# Schematic.net
KiCad netlist of a schematic drawn in Altium Designer
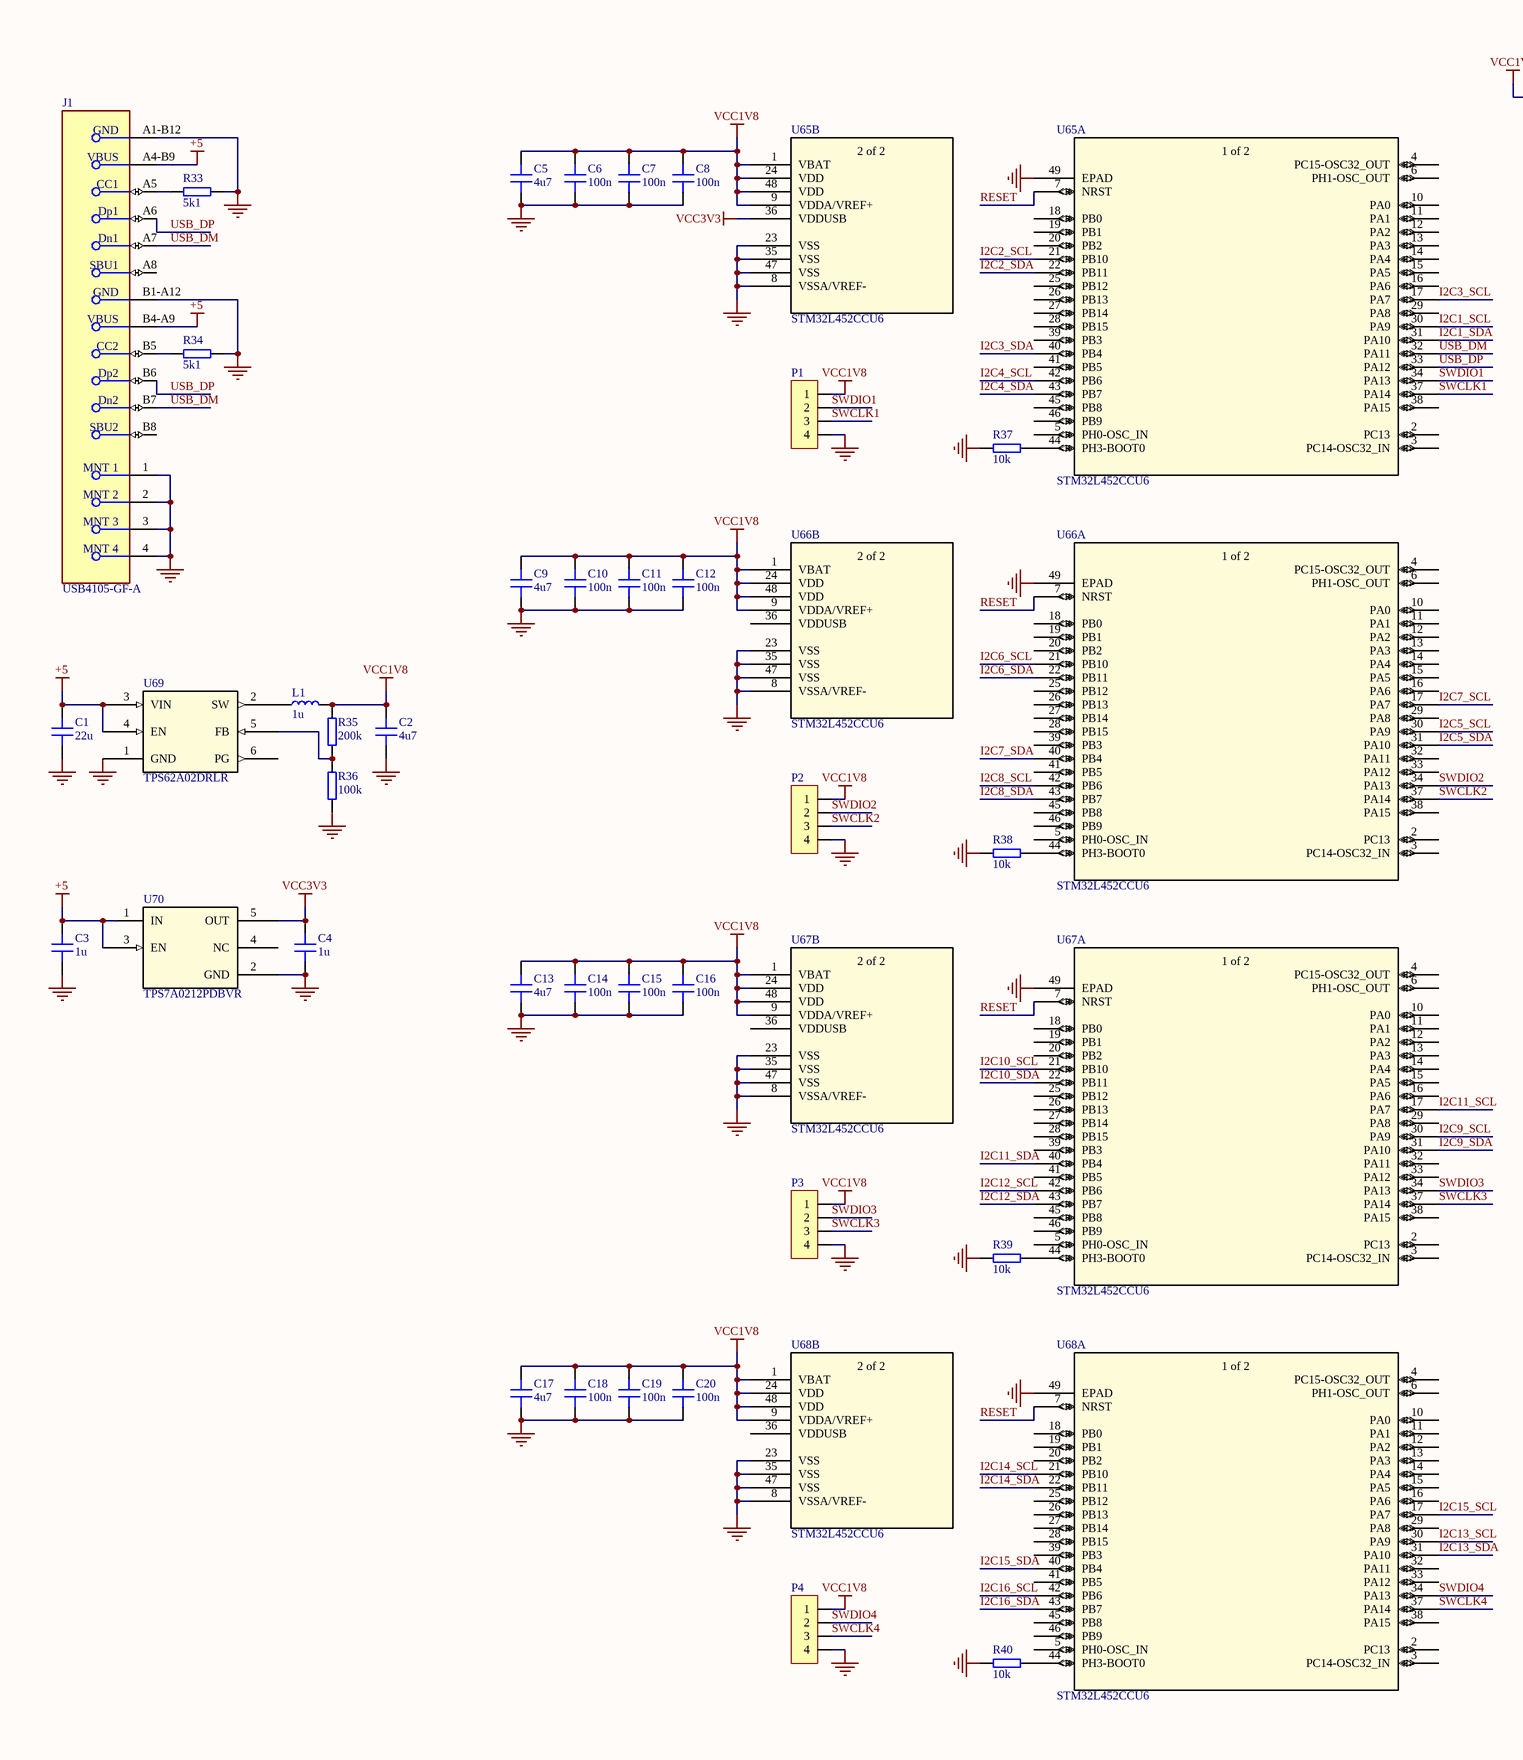
[diagram p0: Schematic.SchDoc, left]
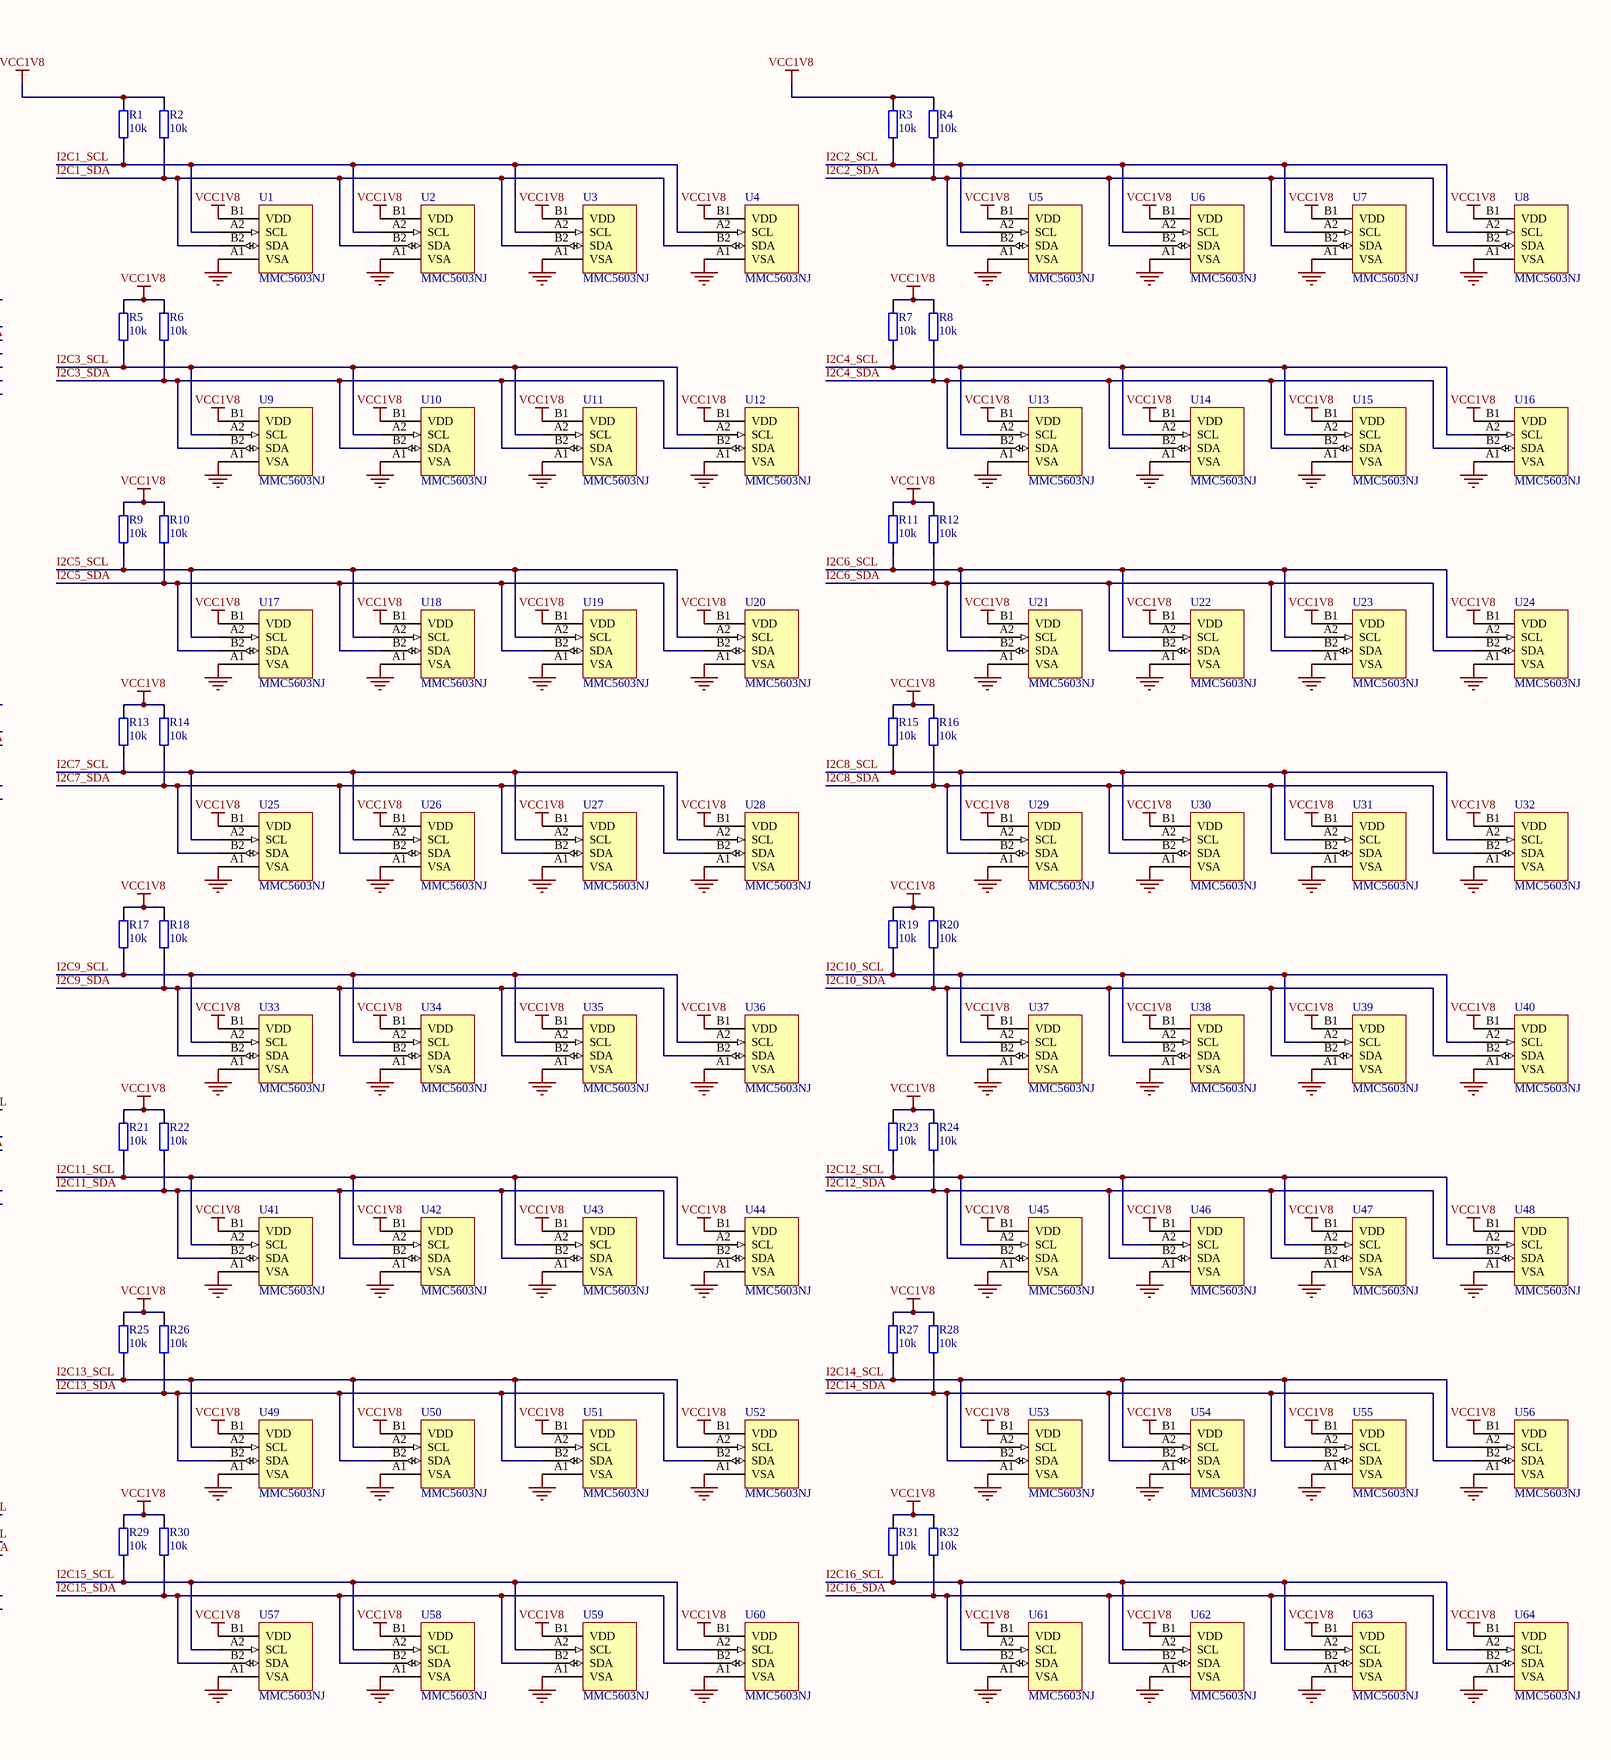
[diagram p1: Schematic.SchDoc, right]

(export (version "E")
  (design (tool "Eeschema 10.0.6"))
  (components
    (comp (ref "C1")
      (value "22u")
      (footprint "CAP_0603")
      (description "Capacitor SMD 0603")
      (fields (field (name "VOLTAGE") "50V"))
      (libsource (lib "symbols") (part "CAP_0603"))
    )
    (comp (ref "C2")
      (value "4u7")
      (footprint "CAP_0603")
      (description "Capacitor SMD 0603")
      (fields (field (name "VOLTAGE") "50V"))
      (libsource (lib "symbols") (part "CAP_0603"))
    )
    (comp (ref "C3")
      (value "1u")
      (footprint "CAP_0603")
      (description "Capacitor SMD 0603")
      (fields (field (name "VOLTAGE") "50V"))
      (libsource (lib "symbols") (part "CAP_0603"))
    )
    (comp (ref "C4")
      (value "1u")
      (footprint "CAP_0603")
      (description "Capacitor SMD 0603")
      (fields (field (name "VOLTAGE") "50V"))
      (libsource (lib "symbols") (part "CAP_0603"))
    )
    (comp (ref "C5")
      (value "4u7")
      (footprint "CAP_0603")
      (description "Capacitor SMD 0603")
      (fields (field (name "VOLTAGE") "50V"))
      (libsource (lib "symbols") (part "CAP_0603"))
    )
    (comp (ref "C6")
      (value "100n")
      (footprint "CAP_0402")
      (description "Capacitor SMD 0402")
      (fields (field (name "VOLTAGE") "50V"))
      (libsource (lib "symbols") (part "CAP_0402"))
    )
    (comp (ref "C7")
      (value "100n")
      (footprint "CAP_0402")
      (description "Capacitor SMD 0402")
      (fields (field (name "VOLTAGE") "50V"))
      (libsource (lib "symbols") (part "CAP_0402"))
    )
    (comp (ref "C8")
      (value "100n")
      (footprint "CAP_0402")
      (description "Capacitor SMD 0402")
      (fields (field (name "VOLTAGE") "50V"))
      (libsource (lib "symbols") (part "CAP_0402"))
    )
    (comp (ref "C9")
      (value "4u7")
      (footprint "CAP_0603")
      (description "Capacitor SMD 0603")
      (fields (field (name "VOLTAGE") "50V"))
      (libsource (lib "symbols") (part "CAP_0603"))
    )
    (comp (ref "C10")
      (value "100n")
      (footprint "CAP_0402")
      (description "Capacitor SMD 0402")
      (fields (field (name "VOLTAGE") "50V"))
      (libsource (lib "symbols") (part "CAP_0402"))
    )
    (comp (ref "C11")
      (value "100n")
      (footprint "CAP_0402")
      (description "Capacitor SMD 0402")
      (fields (field (name "VOLTAGE") "50V"))
      (libsource (lib "symbols") (part "CAP_0402"))
    )
    (comp (ref "C12")
      (value "100n")
      (footprint "CAP_0402")
      (description "Capacitor SMD 0402")
      (fields (field (name "VOLTAGE") "50V"))
      (libsource (lib "symbols") (part "CAP_0402"))
    )
    (comp (ref "C13")
      (value "4u7")
      (footprint "CAP_0603")
      (description "Capacitor SMD 0603")
      (fields (field (name "VOLTAGE") "50V"))
      (libsource (lib "symbols") (part "CAP_0603"))
    )
    (comp (ref "C14")
      (value "100n")
      (footprint "CAP_0402")
      (description "Capacitor SMD 0402")
      (fields (field (name "VOLTAGE") "50V"))
      (libsource (lib "symbols") (part "CAP_0402"))
    )
    (comp (ref "C15")
      (value "100n")
      (footprint "CAP_0402")
      (description "Capacitor SMD 0402")
      (fields (field (name "VOLTAGE") "50V"))
      (libsource (lib "symbols") (part "CAP_0402"))
    )
    (comp (ref "C16")
      (value "100n")
      (footprint "CAP_0402")
      (description "Capacitor SMD 0402")
      (fields (field (name "VOLTAGE") "50V"))
      (libsource (lib "symbols") (part "CAP_0402"))
    )
    (comp (ref "C17")
      (value "4u7")
      (footprint "CAP_0603")
      (description "Capacitor SMD 0603")
      (fields (field (name "VOLTAGE") "50V"))
      (libsource (lib "symbols") (part "CAP_0603"))
    )
    (comp (ref "C18")
      (value "100n")
      (footprint "CAP_0402")
      (description "Capacitor SMD 0402")
      (fields (field (name "VOLTAGE") "50V"))
      (libsource (lib "symbols") (part "CAP_0402"))
    )
    (comp (ref "C19")
      (value "100n")
      (footprint "CAP_0402")
      (description "Capacitor SMD 0402")
      (fields (field (name "VOLTAGE") "50V"))
      (libsource (lib "symbols") (part "CAP_0402"))
    )
    (comp (ref "C20")
      (value "100n")
      (footprint "CAP_0402")
      (description "Capacitor SMD 0402")
      (fields (field (name "VOLTAGE") "50V"))
      (libsource (lib "symbols") (part "CAP_0402"))
    )
    (comp (ref "J1")
      (value "USB4105-GF-A")
      (footprint "FP-USB4105-GF-A-MFG")
      (description "CONN RCPT USB2.0 TYPEC 5A")
      (fields
        (field (name "MANUFACTURER") "GCT")
        (field (name "OCTOPART") "https://octopart.com/usb4105-gf-a-gct-106627878")
      )
      (libsource (lib "symbols") (part "CMP-245163-000001-1"))
    )
    (comp (ref "L1")
      (value "1u")
      (footprint "IND_0603")
      (description "Inductor SMD 0603")
      (libsource (lib "symbols") (part "IND_0603"))
    )
    (comp (ref "P1")
      (value "PIN_1.27x4")
      (footprint "PIN_1.27x4")
      (libsource (lib "symbols") (part "PIN_1.27x4"))
    )
    (comp (ref "P2")
      (value "PIN_1.27x4")
      (footprint "PIN_1.27x4")
      (libsource (lib "symbols") (part "PIN_1.27x4"))
    )
    (comp (ref "P3")
      (value "PIN_1.27x4")
      (footprint "PIN_1.27x4")
      (libsource (lib "symbols") (part "PIN_1.27x4"))
    )
    (comp (ref "P4")
      (value "PIN_1.27x4")
      (footprint "PIN_1.27x4")
      (libsource (lib "symbols") (part "PIN_1.27x4"))
    )
    (comp (ref "R1")
      (value "10k")
      (footprint "RES_0402_RF")
      (description "Resistor SMD 0402")
      (libsource (lib "symbols") (part "RES_0402"))
    )
    (comp (ref "R2")
      (value "10k")
      (footprint "RES_0402_RF")
      (description "Resistor SMD 0402")
      (libsource (lib "symbols") (part "RES_0402"))
    )
    (comp (ref "R3")
      (value "10k")
      (footprint "RES_0402_RF")
      (description "Resistor SMD 0402")
      (libsource (lib "symbols") (part "RES_0402"))
    )
    (comp (ref "R4")
      (value "10k")
      (footprint "RES_0402_RF")
      (description "Resistor SMD 0402")
      (libsource (lib "symbols") (part "RES_0402"))
    )
    (comp (ref "R5")
      (value "10k")
      (footprint "RES_0402_RF")
      (description "Resistor SMD 0402")
      (libsource (lib "symbols") (part "RES_0402"))
    )
    (comp (ref "R6")
      (value "10k")
      (footprint "RES_0402_RF")
      (description "Resistor SMD 0402")
      (libsource (lib "symbols") (part "RES_0402"))
    )
    (comp (ref "R7")
      (value "10k")
      (footprint "RES_0402_RF")
      (description "Resistor SMD 0402")
      (libsource (lib "symbols") (part "RES_0402"))
    )
    (comp (ref "R8")
      (value "10k")
      (footprint "RES_0402_RF")
      (description "Resistor SMD 0402")
      (libsource (lib "symbols") (part "RES_0402"))
    )
    (comp (ref "R9")
      (value "10k")
      (footprint "RES_0402_RF")
      (description "Resistor SMD 0402")
      (libsource (lib "symbols") (part "RES_0402"))
    )
    (comp (ref "R10")
      (value "10k")
      (footprint "RES_0402_RF")
      (description "Resistor SMD 0402")
      (libsource (lib "symbols") (part "RES_0402"))
    )
    (comp (ref "R11")
      (value "10k")
      (footprint "RES_0402_RF")
      (description "Resistor SMD 0402")
      (libsource (lib "symbols") (part "RES_0402"))
    )
    (comp (ref "R12")
      (value "10k")
      (footprint "RES_0402_RF")
      (description "Resistor SMD 0402")
      (libsource (lib "symbols") (part "RES_0402"))
    )
    (comp (ref "R13")
      (value "10k")
      (footprint "RES_0402_RF")
      (description "Resistor SMD 0402")
      (libsource (lib "symbols") (part "RES_0402"))
    )
    (comp (ref "R14")
      (value "10k")
      (footprint "RES_0402_RF")
      (description "Resistor SMD 0402")
      (libsource (lib "symbols") (part "RES_0402"))
    )
    (comp (ref "R15")
      (value "10k")
      (footprint "RES_0402_RF")
      (description "Resistor SMD 0402")
      (libsource (lib "symbols") (part "RES_0402"))
    )
    (comp (ref "R16")
      (value "10k")
      (footprint "RES_0402_RF")
      (description "Resistor SMD 0402")
      (libsource (lib "symbols") (part "RES_0402"))
    )
    (comp (ref "R17")
      (value "10k")
      (footprint "RES_0402_RF")
      (description "Resistor SMD 0402")
      (libsource (lib "symbols") (part "RES_0402"))
    )
    (comp (ref "R18")
      (value "10k")
      (footprint "RES_0402_RF")
      (description "Resistor SMD 0402")
      (libsource (lib "symbols") (part "RES_0402"))
    )
    (comp (ref "R19")
      (value "10k")
      (footprint "RES_0402_RF")
      (description "Resistor SMD 0402")
      (libsource (lib "symbols") (part "RES_0402"))
    )
    (comp (ref "R20")
      (value "10k")
      (footprint "RES_0402_RF")
      (description "Resistor SMD 0402")
      (libsource (lib "symbols") (part "RES_0402"))
    )
    (comp (ref "R21")
      (value "10k")
      (footprint "RES_0402_RF")
      (description "Resistor SMD 0402")
      (libsource (lib "symbols") (part "RES_0402"))
    )
    (comp (ref "R22")
      (value "10k")
      (footprint "RES_0402_RF")
      (description "Resistor SMD 0402")
      (libsource (lib "symbols") (part "RES_0402"))
    )
    (comp (ref "R23")
      (value "10k")
      (footprint "RES_0402_RF")
      (description "Resistor SMD 0402")
      (libsource (lib "symbols") (part "RES_0402"))
    )
    (comp (ref "R24")
      (value "10k")
      (footprint "RES_0402_RF")
      (description "Resistor SMD 0402")
      (libsource (lib "symbols") (part "RES_0402"))
    )
    (comp (ref "R25")
      (value "10k")
      (footprint "RES_0402_RF")
      (description "Resistor SMD 0402")
      (libsource (lib "symbols") (part "RES_0402"))
    )
    (comp (ref "R26")
      (value "10k")
      (footprint "RES_0402_RF")
      (description "Resistor SMD 0402")
      (libsource (lib "symbols") (part "RES_0402"))
    )
    (comp (ref "R27")
      (value "10k")
      (footprint "RES_0402_RF")
      (description "Resistor SMD 0402")
      (libsource (lib "symbols") (part "RES_0402"))
    )
    (comp (ref "R28")
      (value "10k")
      (footprint "RES_0402_RF")
      (description "Resistor SMD 0402")
      (libsource (lib "symbols") (part "RES_0402"))
    )
    (comp (ref "R29")
      (value "10k")
      (footprint "RES_0402_RF")
      (description "Resistor SMD 0402")
      (libsource (lib "symbols") (part "RES_0402"))
    )
    (comp (ref "R30")
      (value "10k")
      (footprint "RES_0402_RF")
      (description "Resistor SMD 0402")
      (libsource (lib "symbols") (part "RES_0402"))
    )
    (comp (ref "R31")
      (value "10k")
      (footprint "RES_0402_RF")
      (description "Resistor SMD 0402")
      (libsource (lib "symbols") (part "RES_0402"))
    )
    (comp (ref "R32")
      (value "10k")
      (footprint "RES_0402_RF")
      (description "Resistor SMD 0402")
      (libsource (lib "symbols") (part "RES_0402"))
    )
    (comp (ref "R33")
      (value "5k1")
      (footprint "RES_0402_RF")
      (description "Resistor SMD 0402")
      (libsource (lib "symbols") (part "RES_0402"))
    )
    (comp (ref "R34")
      (value "5k1")
      (footprint "RES_0402_RF")
      (description "Resistor SMD 0402")
      (libsource (lib "symbols") (part "RES_0402"))
    )
    (comp (ref "R35")
      (value "200k")
      (footprint "RES_0402_RF")
      (description "Resistor SMD 0402")
      (libsource (lib "symbols") (part "RES_0402"))
    )
    (comp (ref "R36")
      (value "100k")
      (footprint "RES_0402_RF")
      (description "Resistor SMD 0402")
      (libsource (lib "symbols") (part "RES_0402"))
    )
    (comp (ref "R37")
      (value "10k")
      (footprint "RES_0402_RF")
      (description "Resistor SMD 0402")
      (libsource (lib "symbols") (part "RES_0402"))
    )
    (comp (ref "R38")
      (value "10k")
      (footprint "RES_0402_RF")
      (description "Resistor SMD 0402")
      (libsource (lib "symbols") (part "RES_0402"))
    )
    (comp (ref "R39")
      (value "10k")
      (footprint "RES_0402_RF")
      (description "Resistor SMD 0402")
      (libsource (lib "symbols") (part "RES_0402"))
    )
    (comp (ref "R40")
      (value "10k")
      (footprint "RES_0402_RF")
      (description "Resistor SMD 0402")
      (libsource (lib "symbols") (part "RES_0402"))
    )
    (comp (ref "U1")
      (value "MMC5603NJ")
      (footprint "WLP4x2")
      (description "3-AXIS Amr Magnetic Sensor")
      (fields (field (name "MANUFACTURER") "Memsic"))
      (libsource (lib "symbols") (part "MMC5603NJ"))
    )
    (comp (ref "U2")
      (value "MMC5603NJ")
      (footprint "WLP4x2")
      (description "3-AXIS Amr Magnetic Sensor")
      (fields (field (name "MANUFACTURER") "Memsic"))
      (libsource (lib "symbols") (part "MMC5603NJ"))
    )
    (comp (ref "U3")
      (value "MMC5603NJ")
      (footprint "WLP4x2")
      (description "3-AXIS Amr Magnetic Sensor")
      (fields (field (name "MANUFACTURER") "Memsic"))
      (libsource (lib "symbols") (part "MMC5603NJ"))
    )
    (comp (ref "U4")
      (value "MMC5603NJ")
      (footprint "WLP4x2")
      (description "3-AXIS Amr Magnetic Sensor")
      (fields (field (name "MANUFACTURER") "Memsic"))
      (libsource (lib "symbols") (part "MMC5603NJ"))
    )
    (comp (ref "U5")
      (value "MMC5603NJ")
      (footprint "WLP4x2")
      (description "3-AXIS Amr Magnetic Sensor")
      (fields (field (name "MANUFACTURER") "Memsic"))
      (libsource (lib "symbols") (part "MMC5603NJ"))
    )
    (comp (ref "U6")
      (value "MMC5603NJ")
      (footprint "WLP4x2")
      (description "3-AXIS Amr Magnetic Sensor")
      (fields (field (name "MANUFACTURER") "Memsic"))
      (libsource (lib "symbols") (part "MMC5603NJ"))
    )
    (comp (ref "U7")
      (value "MMC5603NJ")
      (footprint "WLP4x2")
      (description "3-AXIS Amr Magnetic Sensor")
      (fields (field (name "MANUFACTURER") "Memsic"))
      (libsource (lib "symbols") (part "MMC5603NJ"))
    )
    (comp (ref "U8")
      (value "MMC5603NJ")
      (footprint "WLP4x2")
      (description "3-AXIS Amr Magnetic Sensor")
      (fields (field (name "MANUFACTURER") "Memsic"))
      (libsource (lib "symbols") (part "MMC5603NJ"))
    )
    (comp (ref "U9")
      (value "MMC5603NJ")
      (footprint "WLP4x2")
      (description "3-AXIS Amr Magnetic Sensor")
      (fields (field (name "MANUFACTURER") "Memsic"))
      (libsource (lib "symbols") (part "MMC5603NJ"))
    )
    (comp (ref "U10")
      (value "MMC5603NJ")
      (footprint "WLP4x2")
      (description "3-AXIS Amr Magnetic Sensor")
      (fields (field (name "MANUFACTURER") "Memsic"))
      (libsource (lib "symbols") (part "MMC5603NJ"))
    )
    (comp (ref "U11")
      (value "MMC5603NJ")
      (footprint "WLP4x2")
      (description "3-AXIS Amr Magnetic Sensor")
      (fields (field (name "MANUFACTURER") "Memsic"))
      (libsource (lib "symbols") (part "MMC5603NJ"))
    )
    (comp (ref "U12")
      (value "MMC5603NJ")
      (footprint "WLP4x2")
      (description "3-AXIS Amr Magnetic Sensor")
      (fields (field (name "MANUFACTURER") "Memsic"))
      (libsource (lib "symbols") (part "MMC5603NJ"))
    )
    (comp (ref "U13")
      (value "MMC5603NJ")
      (footprint "WLP4x2")
      (description "3-AXIS Amr Magnetic Sensor")
      (fields (field (name "MANUFACTURER") "Memsic"))
      (libsource (lib "symbols") (part "MMC5603NJ"))
    )
    (comp (ref "U14")
      (value "MMC5603NJ")
      (footprint "WLP4x2")
      (description "3-AXIS Amr Magnetic Sensor")
      (fields (field (name "MANUFACTURER") "Memsic"))
      (libsource (lib "symbols") (part "MMC5603NJ"))
    )
    (comp (ref "U15")
      (value "MMC5603NJ")
      (footprint "WLP4x2")
      (description "3-AXIS Amr Magnetic Sensor")
      (fields (field (name "MANUFACTURER") "Memsic"))
      (libsource (lib "symbols") (part "MMC5603NJ"))
    )
    (comp (ref "U16")
      (value "MMC5603NJ")
      (footprint "WLP4x2")
      (description "3-AXIS Amr Magnetic Sensor")
      (fields (field (name "MANUFACTURER") "Memsic"))
      (libsource (lib "symbols") (part "MMC5603NJ"))
    )
    (comp (ref "U17")
      (value "MMC5603NJ")
      (footprint "WLP4x2")
      (description "3-AXIS Amr Magnetic Sensor")
      (fields (field (name "MANUFACTURER") "Memsic"))
      (libsource (lib "symbols") (part "MMC5603NJ"))
    )
    (comp (ref "U18")
      (value "MMC5603NJ")
      (footprint "WLP4x2")
      (description "3-AXIS Amr Magnetic Sensor")
      (fields (field (name "MANUFACTURER") "Memsic"))
      (libsource (lib "symbols") (part "MMC5603NJ"))
    )
    (comp (ref "U19")
      (value "MMC5603NJ")
      (footprint "WLP4x2")
      (description "3-AXIS Amr Magnetic Sensor")
      (fields (field (name "MANUFACTURER") "Memsic"))
      (libsource (lib "symbols") (part "MMC5603NJ"))
    )
    (comp (ref "U20")
      (value "MMC5603NJ")
      (footprint "WLP4x2")
      (description "3-AXIS Amr Magnetic Sensor")
      (fields (field (name "MANUFACTURER") "Memsic"))
      (libsource (lib "symbols") (part "MMC5603NJ"))
    )
    (comp (ref "U21")
      (value "MMC5603NJ")
      (footprint "WLP4x2")
      (description "3-AXIS Amr Magnetic Sensor")
      (fields (field (name "MANUFACTURER") "Memsic"))
      (libsource (lib "symbols") (part "MMC5603NJ"))
    )
    (comp (ref "U22")
      (value "MMC5603NJ")
      (footprint "WLP4x2")
      (description "3-AXIS Amr Magnetic Sensor")
      (fields (field (name "MANUFACTURER") "Memsic"))
      (libsource (lib "symbols") (part "MMC5603NJ"))
    )
    (comp (ref "U23")
      (value "MMC5603NJ")
      (footprint "WLP4x2")
      (description "3-AXIS Amr Magnetic Sensor")
      (fields (field (name "MANUFACTURER") "Memsic"))
      (libsource (lib "symbols") (part "MMC5603NJ"))
    )
    (comp (ref "U24")
      (value "MMC5603NJ")
      (footprint "WLP4x2")
      (description "3-AXIS Amr Magnetic Sensor")
      (fields (field (name "MANUFACTURER") "Memsic"))
      (libsource (lib "symbols") (part "MMC5603NJ"))
    )
    (comp (ref "U25")
      (value "MMC5603NJ")
      (footprint "WLP4x2")
      (description "3-AXIS Amr Magnetic Sensor")
      (fields (field (name "MANUFACTURER") "Memsic"))
      (libsource (lib "symbols") (part "MMC5603NJ"))
    )
    (comp (ref "U26")
      (value "MMC5603NJ")
      (footprint "WLP4x2")
      (description "3-AXIS Amr Magnetic Sensor")
      (fields (field (name "MANUFACTURER") "Memsic"))
      (libsource (lib "symbols") (part "MMC5603NJ"))
    )
    (comp (ref "U27")
      (value "MMC5603NJ")
      (footprint "WLP4x2")
      (description "3-AXIS Amr Magnetic Sensor")
      (fields (field (name "MANUFACTURER") "Memsic"))
      (libsource (lib "symbols") (part "MMC5603NJ"))
    )
    (comp (ref "U28")
      (value "MMC5603NJ")
      (footprint "WLP4x2")
      (description "3-AXIS Amr Magnetic Sensor")
      (fields (field (name "MANUFACTURER") "Memsic"))
      (libsource (lib "symbols") (part "MMC5603NJ"))
    )
    (comp (ref "U29")
      (value "MMC5603NJ")
      (footprint "WLP4x2")
      (description "3-AXIS Amr Magnetic Sensor")
      (fields (field (name "MANUFACTURER") "Memsic"))
      (libsource (lib "symbols") (part "MMC5603NJ"))
    )
    (comp (ref "U30")
      (value "MMC5603NJ")
      (footprint "WLP4x2")
      (description "3-AXIS Amr Magnetic Sensor")
      (fields (field (name "MANUFACTURER") "Memsic"))
      (libsource (lib "symbols") (part "MMC5603NJ"))
    )
    (comp (ref "U31")
      (value "MMC5603NJ")
      (footprint "WLP4x2")
      (description "3-AXIS Amr Magnetic Sensor")
      (fields (field (name "MANUFACTURER") "Memsic"))
      (libsource (lib "symbols") (part "MMC5603NJ"))
    )
    (comp (ref "U32")
      (value "MMC5603NJ")
      (footprint "WLP4x2")
      (description "3-AXIS Amr Magnetic Sensor")
      (fields (field (name "MANUFACTURER") "Memsic"))
      (libsource (lib "symbols") (part "MMC5603NJ"))
    )
    (comp (ref "U33")
      (value "MMC5603NJ")
      (footprint "WLP4x2")
      (description "3-AXIS Amr Magnetic Sensor")
      (fields (field (name "MANUFACTURER") "Memsic"))
      (libsource (lib "symbols") (part "MMC5603NJ"))
    )
    (comp (ref "U34")
      (value "MMC5603NJ")
      (footprint "WLP4x2")
      (description "3-AXIS Amr Magnetic Sensor")
      (fields (field (name "MANUFACTURER") "Memsic"))
      (libsource (lib "symbols") (part "MMC5603NJ"))
    )
    (comp (ref "U35")
      (value "MMC5603NJ")
      (footprint "WLP4x2")
      (description "3-AXIS Amr Magnetic Sensor")
      (fields (field (name "MANUFACTURER") "Memsic"))
      (libsource (lib "symbols") (part "MMC5603NJ"))
    )
    (comp (ref "U36")
      (value "MMC5603NJ")
      (footprint "WLP4x2")
      (description "3-AXIS Amr Magnetic Sensor")
      (fields (field (name "MANUFACTURER") "Memsic"))
      (libsource (lib "symbols") (part "MMC5603NJ"))
    )
    (comp (ref "U37")
      (value "MMC5603NJ")
      (footprint "WLP4x2")
      (description "3-AXIS Amr Magnetic Sensor")
      (fields (field (name "MANUFACTURER") "Memsic"))
      (libsource (lib "symbols") (part "MMC5603NJ"))
    )
    (comp (ref "U38")
      (value "MMC5603NJ")
      (footprint "WLP4x2")
      (description "3-AXIS Amr Magnetic Sensor")
      (fields (field (name "MANUFACTURER") "Memsic"))
      (libsource (lib "symbols") (part "MMC5603NJ"))
    )
    (comp (ref "U39")
      (value "MMC5603NJ")
      (footprint "WLP4x2")
      (description "3-AXIS Amr Magnetic Sensor")
      (fields (field (name "MANUFACTURER") "Memsic"))
      (libsource (lib "symbols") (part "MMC5603NJ"))
    )
    (comp (ref "U40")
      (value "MMC5603NJ")
      (footprint "WLP4x2")
      (description "3-AXIS Amr Magnetic Sensor")
      (fields (field (name "MANUFACTURER") "Memsic"))
      (libsource (lib "symbols") (part "MMC5603NJ"))
    )
    (comp (ref "U41")
      (value "MMC5603NJ")
      (footprint "WLP4x2")
      (description "3-AXIS Amr Magnetic Sensor")
      (fields (field (name "MANUFACTURER") "Memsic"))
      (libsource (lib "symbols") (part "MMC5603NJ"))
    )
    (comp (ref "U42")
      (value "MMC5603NJ")
      (footprint "WLP4x2")
      (description "3-AXIS Amr Magnetic Sensor")
      (fields (field (name "MANUFACTURER") "Memsic"))
      (libsource (lib "symbols") (part "MMC5603NJ"))
    )
    (comp (ref "U43")
      (value "MMC5603NJ")
      (footprint "WLP4x2")
      (description "3-AXIS Amr Magnetic Sensor")
      (fields (field (name "MANUFACTURER") "Memsic"))
      (libsource (lib "symbols") (part "MMC5603NJ"))
    )
    (comp (ref "U44")
      (value "MMC5603NJ")
      (footprint "WLP4x2")
      (description "3-AXIS Amr Magnetic Sensor")
      (fields (field (name "MANUFACTURER") "Memsic"))
      (libsource (lib "symbols") (part "MMC5603NJ"))
    )
    (comp (ref "U45")
      (value "MMC5603NJ")
      (footprint "WLP4x2")
      (description "3-AXIS Amr Magnetic Sensor")
      (fields (field (name "MANUFACTURER") "Memsic"))
      (libsource (lib "symbols") (part "MMC5603NJ"))
    )
    (comp (ref "U46")
      (value "MMC5603NJ")
      (footprint "WLP4x2")
      (description "3-AXIS Amr Magnetic Sensor")
      (fields (field (name "MANUFACTURER") "Memsic"))
      (libsource (lib "symbols") (part "MMC5603NJ"))
    )
    (comp (ref "U47")
      (value "MMC5603NJ")
      (footprint "WLP4x2")
      (description "3-AXIS Amr Magnetic Sensor")
      (fields (field (name "MANUFACTURER") "Memsic"))
      (libsource (lib "symbols") (part "MMC5603NJ"))
    )
    (comp (ref "U48")
      (value "MMC5603NJ")
      (footprint "WLP4x2")
      (description "3-AXIS Amr Magnetic Sensor")
      (fields (field (name "MANUFACTURER") "Memsic"))
      (libsource (lib "symbols") (part "MMC5603NJ"))
    )
    (comp (ref "U49")
      (value "MMC5603NJ")
      (footprint "WLP4x2")
      (description "3-AXIS Amr Magnetic Sensor")
      (fields (field (name "MANUFACTURER") "Memsic"))
      (libsource (lib "symbols") (part "MMC5603NJ"))
    )
    (comp (ref "U50")
      (value "MMC5603NJ")
      (footprint "WLP4x2")
      (description "3-AXIS Amr Magnetic Sensor")
      (fields (field (name "MANUFACTURER") "Memsic"))
      (libsource (lib "symbols") (part "MMC5603NJ"))
    )
    (comp (ref "U51")
      (value "MMC5603NJ")
      (footprint "WLP4x2")
      (description "3-AXIS Amr Magnetic Sensor")
      (fields (field (name "MANUFACTURER") "Memsic"))
      (libsource (lib "symbols") (part "MMC5603NJ"))
    )
    (comp (ref "U52")
      (value "MMC5603NJ")
      (footprint "WLP4x2")
      (description "3-AXIS Amr Magnetic Sensor")
      (fields (field (name "MANUFACTURER") "Memsic"))
      (libsource (lib "symbols") (part "MMC5603NJ"))
    )
    (comp (ref "U53")
      (value "MMC5603NJ")
      (footprint "WLP4x2")
      (description "3-AXIS Amr Magnetic Sensor")
      (fields (field (name "MANUFACTURER") "Memsic"))
      (libsource (lib "symbols") (part "MMC5603NJ"))
    )
    (comp (ref "U54")
      (value "MMC5603NJ")
      (footprint "WLP4x2")
      (description "3-AXIS Amr Magnetic Sensor")
      (fields (field (name "MANUFACTURER") "Memsic"))
      (libsource (lib "symbols") (part "MMC5603NJ"))
    )
    (comp (ref "U55")
      (value "MMC5603NJ")
      (footprint "WLP4x2")
      (description "3-AXIS Amr Magnetic Sensor")
      (fields (field (name "MANUFACTURER") "Memsic"))
      (libsource (lib "symbols") (part "MMC5603NJ"))
    )
    (comp (ref "U56")
      (value "MMC5603NJ")
      (footprint "WLP4x2")
      (description "3-AXIS Amr Magnetic Sensor")
      (fields (field (name "MANUFACTURER") "Memsic"))
      (libsource (lib "symbols") (part "MMC5603NJ"))
    )
    (comp (ref "U57")
      (value "MMC5603NJ")
      (footprint "WLP4x2")
      (description "3-AXIS Amr Magnetic Sensor")
      (fields (field (name "MANUFACTURER") "Memsic"))
      (libsource (lib "symbols") (part "MMC5603NJ"))
    )
    (comp (ref "U58")
      (value "MMC5603NJ")
      (footprint "WLP4x2")
      (description "3-AXIS Amr Magnetic Sensor")
      (fields (field (name "MANUFACTURER") "Memsic"))
      (libsource (lib "symbols") (part "MMC5603NJ"))
    )
    (comp (ref "U59")
      (value "MMC5603NJ")
      (footprint "WLP4x2")
      (description "3-AXIS Amr Magnetic Sensor")
      (fields (field (name "MANUFACTURER") "Memsic"))
      (libsource (lib "symbols") (part "MMC5603NJ"))
    )
    (comp (ref "U60")
      (value "MMC5603NJ")
      (footprint "WLP4x2")
      (description "3-AXIS Amr Magnetic Sensor")
      (fields (field (name "MANUFACTURER") "Memsic"))
      (libsource (lib "symbols") (part "MMC5603NJ"))
    )
    (comp (ref "U61")
      (value "MMC5603NJ")
      (footprint "WLP4x2")
      (description "3-AXIS Amr Magnetic Sensor")
      (fields (field (name "MANUFACTURER") "Memsic"))
      (libsource (lib "symbols") (part "MMC5603NJ"))
    )
    (comp (ref "U62")
      (value "MMC5603NJ")
      (footprint "WLP4x2")
      (description "3-AXIS Amr Magnetic Sensor")
      (fields (field (name "MANUFACTURER") "Memsic"))
      (libsource (lib "symbols") (part "MMC5603NJ"))
    )
    (comp (ref "U63")
      (value "MMC5603NJ")
      (footprint "WLP4x2")
      (description "3-AXIS Amr Magnetic Sensor")
      (fields (field (name "MANUFACTURER") "Memsic"))
      (libsource (lib "symbols") (part "MMC5603NJ"))
    )
    (comp (ref "U64")
      (value "MMC5603NJ")
      (footprint "WLP4x2")
      (description "3-AXIS Amr Magnetic Sensor")
      (fields (field (name "MANUFACTURER") "Memsic"))
      (libsource (lib "symbols") (part "MMC5603NJ"))
    )
    (comp (ref "U65")
      (value "STM32L452CCU6")
      (footprint "UFQFPN48-7x7mm_STM")
      (description "No Description Available")
      (fields (field (name "COPYRIGHT") "Copyright (C) 2023 Ultra Librarian. All rights reserved."))
      (libsource (lib "symbols") (part "STM32L452CCU6"))
    )
    (comp (ref "U66")
      (value "STM32L452CCU6")
      (footprint "UFQFPN48-7x7mm_STM")
      (description "No Description Available")
      (fields (field (name "COPYRIGHT") "Copyright (C) 2023 Ultra Librarian. All rights reserved."))
      (libsource (lib "symbols") (part "STM32L452CCU6"))
    )
    (comp (ref "U67")
      (value "STM32L452CCU6")
      (footprint "UFQFPN48-7x7mm_STM")
      (description "No Description Available")
      (fields (field (name "COPYRIGHT") "Copyright (C) 2023 Ultra Librarian. All rights reserved."))
      (libsource (lib "symbols") (part "STM32L452CCU6"))
    )
    (comp (ref "U68")
      (value "STM32L452CCU6")
      (footprint "UFQFPN48-7x7mm_STM")
      (description "No Description Available")
      (fields (field (name "COPYRIGHT") "Copyright (C) 2023 Ultra Librarian. All rights reserved."))
      (libsource (lib "symbols") (part "STM32L452CCU6"))
    )
    (comp (ref "U69")
      (value "TPS62A02DRLR")
      (footprint "SOT-5X3-6_DRL_TEX")
      (description "No Description Available")
      (fields (field (name "COPYRIGHT") "Copyright (C) 2023 Ultra Librarian. All rights reserved."))
      (libsource (lib "symbols") (part "TPS62A02DRLR"))
    )
    (comp (ref "U70")
      (value "TPS7A0212PDBVR")
      (footprint "SOT23_DBV_TEX")
      (description "No Description Available")
      (fields (field (name "COPYRIGHT") "Copyright (C) 2023 Ultra Librarian. All rights reserved."))
      (libsource (lib "symbols") (part "TPS7A0212PDBVR"))
    )
  )
  (nets
    (net (code "1") (name "+5") (class "Default")
      (node (ref "C1") (pin "2") (pinfunction "2_2") (pintype "passive"))
      (node (ref "C3") (pin "2") (pinfunction "2_2") (pintype "passive"))
      (node (ref "J1") (pin "A4-B9") (pinfunction "VBUS_A4-B9") (pintype "power_in"))
      (node (ref "J1") (pin "B4-A9") (pinfunction "VBUS_B4-A9") (pintype "power_in"))
      (node (ref "U69") (pin "3") (pinfunction "VIN_3") (pintype "input"))
      (node (ref "U69") (pin "4") (pinfunction "EN_4") (pintype "input"))
      (node (ref "U70") (pin "1") (pinfunction "IN_1") (pintype "power_in"))
      (node (ref "U70") (pin "3") (pinfunction "EN_3") (pintype "input"))
    )
    (net (code "2") (name "/I2C1_SCL") (class "Default")
      (node (ref "R1") (pin "1") (pinfunction "1_1") (pintype "passive"))
      (node (ref "U1") (pin "A2") (pinfunction "SCL_A2") (pintype "input"))
      (node (ref "U2") (pin "A2") (pinfunction "SCL_A2") (pintype "input"))
      (node (ref "U3") (pin "A2") (pinfunction "SCL_A2") (pintype "input"))
      (node (ref "U4") (pin "A2") (pinfunction "SCL_A2") (pintype "input"))
      (node (ref "U65") (pin "30") (pinfunction "PA9_30") (pintype "bidirectional"))
    )
    (net (code "3") (name "/I2C1_SDA") (class "Default")
      (node (ref "R2") (pin "1") (pinfunction "1_1") (pintype "passive"))
      (node (ref "U1") (pin "B2") (pinfunction "SDA_B2") (pintype "bidirectional"))
      (node (ref "U2") (pin "B2") (pinfunction "SDA_B2") (pintype "bidirectional"))
      (node (ref "U3") (pin "B2") (pinfunction "SDA_B2") (pintype "bidirectional"))
      (node (ref "U4") (pin "B2") (pinfunction "SDA_B2") (pintype "bidirectional"))
      (node (ref "U65") (pin "31") (pinfunction "PA10_31") (pintype "bidirectional"))
    )
    (net (code "4") (name "/I2C2_SCL") (class "Default")
      (node (ref "R3") (pin "1") (pinfunction "1_1") (pintype "passive"))
      (node (ref "U5") (pin "A2") (pinfunction "SCL_A2") (pintype "input"))
      (node (ref "U6") (pin "A2") (pinfunction "SCL_A2") (pintype "input"))
      (node (ref "U65") (pin "21") (pinfunction "PB10_21") (pintype "bidirectional"))
      (node (ref "U7") (pin "A2") (pinfunction "SCL_A2") (pintype "input"))
      (node (ref "U8") (pin "A2") (pinfunction "SCL_A2") (pintype "input"))
    )
    (net (code "5") (name "/I2C2_SDA") (class "Default")
      (node (ref "R4") (pin "1") (pinfunction "1_1") (pintype "passive"))
      (node (ref "U5") (pin "B2") (pinfunction "SDA_B2") (pintype "bidirectional"))
      (node (ref "U6") (pin "B2") (pinfunction "SDA_B2") (pintype "bidirectional"))
      (node (ref "U65") (pin "22") (pinfunction "PB11_22") (pintype "bidirectional"))
      (node (ref "U7") (pin "B2") (pinfunction "SDA_B2") (pintype "bidirectional"))
      (node (ref "U8") (pin "B2") (pinfunction "SDA_B2") (pintype "bidirectional"))
    )
    (net (code "6") (name "/I2C3_SCL") (class "Default")
      (node (ref "R5") (pin "1") (pinfunction "1_1") (pintype "passive"))
      (node (ref "U10") (pin "A2") (pinfunction "SCL_A2") (pintype "input"))
      (node (ref "U11") (pin "A2") (pinfunction "SCL_A2") (pintype "input"))
      (node (ref "U12") (pin "A2") (pinfunction "SCL_A2") (pintype "input"))
      (node (ref "U65") (pin "17") (pinfunction "PA7_17") (pintype "bidirectional"))
      (node (ref "U9") (pin "A2") (pinfunction "SCL_A2") (pintype "input"))
    )
    (net (code "7") (name "/I2C3_SDA") (class "Default")
      (node (ref "R6") (pin "1") (pinfunction "1_1") (pintype "passive"))
      (node (ref "U10") (pin "B2") (pinfunction "SDA_B2") (pintype "bidirectional"))
      (node (ref "U11") (pin "B2") (pinfunction "SDA_B2") (pintype "bidirectional"))
      (node (ref "U12") (pin "B2") (pinfunction "SDA_B2") (pintype "bidirectional"))
      (node (ref "U65") (pin "40") (pinfunction "PB4_40") (pintype "bidirectional"))
      (node (ref "U9") (pin "B2") (pinfunction "SDA_B2") (pintype "bidirectional"))
    )
    (net (code "8") (name "/I2C4_SCL") (class "Default")
      (node (ref "R7") (pin "1") (pinfunction "1_1") (pintype "passive"))
      (node (ref "U13") (pin "A2") (pinfunction "SCL_A2") (pintype "input"))
      (node (ref "U14") (pin "A2") (pinfunction "SCL_A2") (pintype "input"))
      (node (ref "U15") (pin "A2") (pinfunction "SCL_A2") (pintype "input"))
      (node (ref "U16") (pin "A2") (pinfunction "SCL_A2") (pintype "input"))
      (node (ref "U65") (pin "42") (pinfunction "PB6_42") (pintype "bidirectional"))
    )
    (net (code "9") (name "/I2C4_SDA") (class "Default")
      (node (ref "R8") (pin "1") (pinfunction "1_1") (pintype "passive"))
      (node (ref "U13") (pin "B2") (pinfunction "SDA_B2") (pintype "bidirectional"))
      (node (ref "U14") (pin "B2") (pinfunction "SDA_B2") (pintype "bidirectional"))
      (node (ref "U15") (pin "B2") (pinfunction "SDA_B2") (pintype "bidirectional"))
      (node (ref "U16") (pin "B2") (pinfunction "SDA_B2") (pintype "bidirectional"))
      (node (ref "U65") (pin "43") (pinfunction "PB7_43") (pintype "bidirectional"))
    )
    (net (code "10") (name "/I2C5_SCL") (class "Default")
      (node (ref "R9") (pin "1") (pinfunction "1_1") (pintype "passive"))
      (node (ref "U17") (pin "A2") (pinfunction "SCL_A2") (pintype "input"))
      (node (ref "U18") (pin "A2") (pinfunction "SCL_A2") (pintype "input"))
      (node (ref "U19") (pin "A2") (pinfunction "SCL_A2") (pintype "input"))
      (node (ref "U20") (pin "A2") (pinfunction "SCL_A2") (pintype "input"))
      (node (ref "U66") (pin "30") (pinfunction "PA9_30") (pintype "bidirectional"))
    )
    (net (code "11") (name "/I2C5_SDA") (class "Default")
      (node (ref "R10") (pin "1") (pinfunction "1_1") (pintype "passive"))
      (node (ref "U17") (pin "B2") (pinfunction "SDA_B2") (pintype "bidirectional"))
      (node (ref "U18") (pin "B2") (pinfunction "SDA_B2") (pintype "bidirectional"))
      (node (ref "U19") (pin "B2") (pinfunction "SDA_B2") (pintype "bidirectional"))
      (node (ref "U20") (pin "B2") (pinfunction "SDA_B2") (pintype "bidirectional"))
      (node (ref "U66") (pin "31") (pinfunction "PA10_31") (pintype "bidirectional"))
    )
    (net (code "12") (name "/I2C6_SCL") (class "Default")
      (node (ref "R11") (pin "1") (pinfunction "1_1") (pintype "passive"))
      (node (ref "U21") (pin "A2") (pinfunction "SCL_A2") (pintype "input"))
      (node (ref "U22") (pin "A2") (pinfunction "SCL_A2") (pintype "input"))
      (node (ref "U23") (pin "A2") (pinfunction "SCL_A2") (pintype "input"))
      (node (ref "U24") (pin "A2") (pinfunction "SCL_A2") (pintype "input"))
      (node (ref "U66") (pin "21") (pinfunction "PB10_21") (pintype "bidirectional"))
    )
    (net (code "13") (name "/I2C6_SDA") (class "Default")
      (node (ref "R12") (pin "1") (pinfunction "1_1") (pintype "passive"))
      (node (ref "U21") (pin "B2") (pinfunction "SDA_B2") (pintype "bidirectional"))
      (node (ref "U22") (pin "B2") (pinfunction "SDA_B2") (pintype "bidirectional"))
      (node (ref "U23") (pin "B2") (pinfunction "SDA_B2") (pintype "bidirectional"))
      (node (ref "U24") (pin "B2") (pinfunction "SDA_B2") (pintype "bidirectional"))
      (node (ref "U66") (pin "22") (pinfunction "PB11_22") (pintype "bidirectional"))
    )
    (net (code "14") (name "/I2C7_SCL") (class "Default")
      (node (ref "R13") (pin "1") (pinfunction "1_1") (pintype "passive"))
      (node (ref "U25") (pin "A2") (pinfunction "SCL_A2") (pintype "input"))
      (node (ref "U26") (pin "A2") (pinfunction "SCL_A2") (pintype "input"))
      (node (ref "U27") (pin "A2") (pinfunction "SCL_A2") (pintype "input"))
      (node (ref "U28") (pin "A2") (pinfunction "SCL_A2") (pintype "input"))
      (node (ref "U66") (pin "17") (pinfunction "PA7_17") (pintype "bidirectional"))
    )
    (net (code "15") (name "/I2C7_SDA") (class "Default")
      (node (ref "R14") (pin "1") (pinfunction "1_1") (pintype "passive"))
      (node (ref "U25") (pin "B2") (pinfunction "SDA_B2") (pintype "bidirectional"))
      (node (ref "U26") (pin "B2") (pinfunction "SDA_B2") (pintype "bidirectional"))
      (node (ref "U27") (pin "B2") (pinfunction "SDA_B2") (pintype "bidirectional"))
      (node (ref "U28") (pin "B2") (pinfunction "SDA_B2") (pintype "bidirectional"))
      (node (ref "U66") (pin "40") (pinfunction "PB4_40") (pintype "bidirectional"))
    )
    (net (code "16") (name "/I2C8_SCL") (class "Default")
      (node (ref "R15") (pin "1") (pinfunction "1_1") (pintype "passive"))
      (node (ref "U29") (pin "A2") (pinfunction "SCL_A2") (pintype "input"))
      (node (ref "U30") (pin "A2") (pinfunction "SCL_A2") (pintype "input"))
      (node (ref "U31") (pin "A2") (pinfunction "SCL_A2") (pintype "input"))
      (node (ref "U32") (pin "A2") (pinfunction "SCL_A2") (pintype "input"))
      (node (ref "U66") (pin "42") (pinfunction "PB6_42") (pintype "bidirectional"))
    )
    (net (code "17") (name "/I2C8_SDA") (class "Default")
      (node (ref "R16") (pin "1") (pinfunction "1_1") (pintype "passive"))
      (node (ref "U29") (pin "B2") (pinfunction "SDA_B2") (pintype "bidirectional"))
      (node (ref "U30") (pin "B2") (pinfunction "SDA_B2") (pintype "bidirectional"))
      (node (ref "U31") (pin "B2") (pinfunction "SDA_B2") (pintype "bidirectional"))
      (node (ref "U32") (pin "B2") (pinfunction "SDA_B2") (pintype "bidirectional"))
      (node (ref "U66") (pin "43") (pinfunction "PB7_43") (pintype "bidirectional"))
    )
    (net (code "18") (name "/I2C9_SCL") (class "Default")
      (node (ref "R17") (pin "1") (pinfunction "1_1") (pintype "passive"))
      (node (ref "U33") (pin "A2") (pinfunction "SCL_A2") (pintype "input"))
      (node (ref "U34") (pin "A2") (pinfunction "SCL_A2") (pintype "input"))
      (node (ref "U35") (pin "A2") (pinfunction "SCL_A2") (pintype "input"))
      (node (ref "U36") (pin "A2") (pinfunction "SCL_A2") (pintype "input"))
      (node (ref "U67") (pin "30") (pinfunction "PA9_30") (pintype "bidirectional"))
    )
    (net (code "19") (name "/I2C9_SDA") (class "Default")
      (node (ref "R18") (pin "1") (pinfunction "1_1") (pintype "passive"))
      (node (ref "U33") (pin "B2") (pinfunction "SDA_B2") (pintype "bidirectional"))
      (node (ref "U34") (pin "B2") (pinfunction "SDA_B2") (pintype "bidirectional"))
      (node (ref "U35") (pin "B2") (pinfunction "SDA_B2") (pintype "bidirectional"))
      (node (ref "U36") (pin "B2") (pinfunction "SDA_B2") (pintype "bidirectional"))
      (node (ref "U67") (pin "31") (pinfunction "PA10_31") (pintype "bidirectional"))
    )
    (net (code "20") (name "/I2C10_SCL") (class "Default")
      (node (ref "R19") (pin "1") (pinfunction "1_1") (pintype "passive"))
      (node (ref "U37") (pin "A2") (pinfunction "SCL_A2") (pintype "input"))
      (node (ref "U38") (pin "A2") (pinfunction "SCL_A2") (pintype "input"))
      (node (ref "U39") (pin "A2") (pinfunction "SCL_A2") (pintype "input"))
      (node (ref "U40") (pin "A2") (pinfunction "SCL_A2") (pintype "input"))
      (node (ref "U67") (pin "21") (pinfunction "PB10_21") (pintype "bidirectional"))
    )
    (net (code "21") (name "/I2C10_SDA") (class "Default")
      (node (ref "R20") (pin "1") (pinfunction "1_1") (pintype "passive"))
      (node (ref "U37") (pin "B2") (pinfunction "SDA_B2") (pintype "bidirectional"))
      (node (ref "U38") (pin "B2") (pinfunction "SDA_B2") (pintype "bidirectional"))
      (node (ref "U39") (pin "B2") (pinfunction "SDA_B2") (pintype "bidirectional"))
      (node (ref "U40") (pin "B2") (pinfunction "SDA_B2") (pintype "bidirectional"))
      (node (ref "U67") (pin "22") (pinfunction "PB11_22") (pintype "bidirectional"))
    )
    (net (code "22") (name "/I2C11_SCL") (class "Default")
      (node (ref "R21") (pin "1") (pinfunction "1_1") (pintype "passive"))
      (node (ref "U41") (pin "A2") (pinfunction "SCL_A2") (pintype "input"))
      (node (ref "U42") (pin "A2") (pinfunction "SCL_A2") (pintype "input"))
      (node (ref "U43") (pin "A2") (pinfunction "SCL_A2") (pintype "input"))
      (node (ref "U44") (pin "A2") (pinfunction "SCL_A2") (pintype "input"))
      (node (ref "U67") (pin "17") (pinfunction "PA7_17") (pintype "bidirectional"))
    )
    (net (code "23") (name "/I2C11_SDA") (class "Default")
      (node (ref "R22") (pin "1") (pinfunction "1_1") (pintype "passive"))
      (node (ref "U41") (pin "B2") (pinfunction "SDA_B2") (pintype "bidirectional"))
      (node (ref "U42") (pin "B2") (pinfunction "SDA_B2") (pintype "bidirectional"))
      (node (ref "U43") (pin "B2") (pinfunction "SDA_B2") (pintype "bidirectional"))
      (node (ref "U44") (pin "B2") (pinfunction "SDA_B2") (pintype "bidirectional"))
      (node (ref "U67") (pin "40") (pinfunction "PB4_40") (pintype "bidirectional"))
    )
    (net (code "24") (name "/I2C12_SCL") (class "Default")
      (node (ref "R23") (pin "1") (pinfunction "1_1") (pintype "passive"))
      (node (ref "U45") (pin "A2") (pinfunction "SCL_A2") (pintype "input"))
      (node (ref "U46") (pin "A2") (pinfunction "SCL_A2") (pintype "input"))
      (node (ref "U47") (pin "A2") (pinfunction "SCL_A2") (pintype "input"))
      (node (ref "U48") (pin "A2") (pinfunction "SCL_A2") (pintype "input"))
      (node (ref "U67") (pin "42") (pinfunction "PB6_42") (pintype "bidirectional"))
    )
    (net (code "25") (name "/I2C12_SDA") (class "Default")
      (node (ref "R24") (pin "1") (pinfunction "1_1") (pintype "passive"))
      (node (ref "U45") (pin "B2") (pinfunction "SDA_B2") (pintype "bidirectional"))
      (node (ref "U46") (pin "B2") (pinfunction "SDA_B2") (pintype "bidirectional"))
      (node (ref "U47") (pin "B2") (pinfunction "SDA_B2") (pintype "bidirectional"))
      (node (ref "U48") (pin "B2") (pinfunction "SDA_B2") (pintype "bidirectional"))
      (node (ref "U67") (pin "43") (pinfunction "PB7_43") (pintype "bidirectional"))
    )
    (net (code "26") (name "/I2C13_SCL") (class "Default")
      (node (ref "R25") (pin "1") (pinfunction "1_1") (pintype "passive"))
      (node (ref "U49") (pin "A2") (pinfunction "SCL_A2") (pintype "input"))
      (node (ref "U50") (pin "A2") (pinfunction "SCL_A2") (pintype "input"))
      (node (ref "U51") (pin "A2") (pinfunction "SCL_A2") (pintype "input"))
      (node (ref "U52") (pin "A2") (pinfunction "SCL_A2") (pintype "input"))
      (node (ref "U68") (pin "30") (pinfunction "PA9_30") (pintype "bidirectional"))
    )
    (net (code "27") (name "/I2C13_SDA") (class "Default")
      (node (ref "R26") (pin "1") (pinfunction "1_1") (pintype "passive"))
      (node (ref "U49") (pin "B2") (pinfunction "SDA_B2") (pintype "bidirectional"))
      (node (ref "U50") (pin "B2") (pinfunction "SDA_B2") (pintype "bidirectional"))
      (node (ref "U51") (pin "B2") (pinfunction "SDA_B2") (pintype "bidirectional"))
      (node (ref "U52") (pin "B2") (pinfunction "SDA_B2") (pintype "bidirectional"))
      (node (ref "U68") (pin "31") (pinfunction "PA10_31") (pintype "bidirectional"))
    )
    (net (code "28") (name "/I2C14_SCL") (class "Default")
      (node (ref "R27") (pin "1") (pinfunction "1_1") (pintype "passive"))
      (node (ref "U53") (pin "A2") (pinfunction "SCL_A2") (pintype "input"))
      (node (ref "U54") (pin "A2") (pinfunction "SCL_A2") (pintype "input"))
      (node (ref "U55") (pin "A2") (pinfunction "SCL_A2") (pintype "input"))
      (node (ref "U56") (pin "A2") (pinfunction "SCL_A2") (pintype "input"))
      (node (ref "U68") (pin "21") (pinfunction "PB10_21") (pintype "bidirectional"))
    )
    (net (code "29") (name "/I2C14_SDA") (class "Default")
      (node (ref "R28") (pin "1") (pinfunction "1_1") (pintype "passive"))
      (node (ref "U53") (pin "B2") (pinfunction "SDA_B2") (pintype "bidirectional"))
      (node (ref "U54") (pin "B2") (pinfunction "SDA_B2") (pintype "bidirectional"))
      (node (ref "U55") (pin "B2") (pinfunction "SDA_B2") (pintype "bidirectional"))
      (node (ref "U56") (pin "B2") (pinfunction "SDA_B2") (pintype "bidirectional"))
      (node (ref "U68") (pin "22") (pinfunction "PB11_22") (pintype "bidirectional"))
    )
    (net (code "30") (name "/I2C15_SCL") (class "Default")
      (node (ref "R29") (pin "1") (pinfunction "1_1") (pintype "passive"))
      (node (ref "U57") (pin "A2") (pinfunction "SCL_A2") (pintype "input"))
      (node (ref "U58") (pin "A2") (pinfunction "SCL_A2") (pintype "input"))
      (node (ref "U59") (pin "A2") (pinfunction "SCL_A2") (pintype "input"))
      (node (ref "U60") (pin "A2") (pinfunction "SCL_A2") (pintype "input"))
      (node (ref "U68") (pin "17") (pinfunction "PA7_17") (pintype "bidirectional"))
    )
    (net (code "31") (name "/I2C15_SDA") (class "Default")
      (node (ref "R30") (pin "1") (pinfunction "1_1") (pintype "passive"))
      (node (ref "U57") (pin "B2") (pinfunction "SDA_B2") (pintype "bidirectional"))
      (node (ref "U58") (pin "B2") (pinfunction "SDA_B2") (pintype "bidirectional"))
      (node (ref "U59") (pin "B2") (pinfunction "SDA_B2") (pintype "bidirectional"))
      (node (ref "U60") (pin "B2") (pinfunction "SDA_B2") (pintype "bidirectional"))
      (node (ref "U68") (pin "40") (pinfunction "PB4_40") (pintype "bidirectional"))
    )
    (net (code "32") (name "/I2C16_SCL") (class "Default")
      (node (ref "R31") (pin "1") (pinfunction "1_1") (pintype "passive"))
      (node (ref "U61") (pin "A2") (pinfunction "SCL_A2") (pintype "input"))
      (node (ref "U62") (pin "A2") (pinfunction "SCL_A2") (pintype "input"))
      (node (ref "U63") (pin "A2") (pinfunction "SCL_A2") (pintype "input"))
      (node (ref "U64") (pin "A2") (pinfunction "SCL_A2") (pintype "input"))
      (node (ref "U68") (pin "42") (pinfunction "PB6_42") (pintype "bidirectional"))
    )
    (net (code "33") (name "/I2C16_SDA") (class "Default")
      (node (ref "R32") (pin "1") (pinfunction "1_1") (pintype "passive"))
      (node (ref "U61") (pin "B2") (pinfunction "SDA_B2") (pintype "bidirectional"))
      (node (ref "U62") (pin "B2") (pinfunction "SDA_B2") (pintype "bidirectional"))
      (node (ref "U63") (pin "B2") (pinfunction "SDA_B2") (pintype "bidirectional"))
      (node (ref "U64") (pin "B2") (pinfunction "SDA_B2") (pintype "bidirectional"))
      (node (ref "U68") (pin "43") (pinfunction "PB7_43") (pintype "bidirectional"))
    )
    (net (code "34") (name "/RESET") (class "Default")
      (node (ref "U65") (pin "7") (pinfunction "NRST_7") (pintype "bidirectional"))
      (node (ref "U66") (pin "7") (pinfunction "NRST_7") (pintype "bidirectional"))
      (node (ref "U67") (pin "7") (pinfunction "NRST_7") (pintype "bidirectional"))
      (node (ref "U68") (pin "7") (pinfunction "NRST_7") (pintype "bidirectional"))
    )
    (net (code "35") (name "/SWCLK1") (class "Default")
      (node (ref "P1") (pin "3") (pinfunction "3_3") (pintype "passive"))
      (node (ref "U65") (pin "37") (pinfunction "PA14_37") (pintype "bidirectional"))
    )
    (net (code "36") (name "/SWCLK2") (class "Default")
      (node (ref "P2") (pin "3") (pinfunction "3_3") (pintype "passive"))
      (node (ref "U66") (pin "37") (pinfunction "PA14_37") (pintype "bidirectional"))
    )
    (net (code "37") (name "/SWCLK3") (class "Default")
      (node (ref "P3") (pin "3") (pinfunction "3_3") (pintype "passive"))
      (node (ref "U67") (pin "37") (pinfunction "PA14_37") (pintype "bidirectional"))
    )
    (net (code "38") (name "/SWCLK4") (class "Default")
      (node (ref "P4") (pin "3") (pinfunction "3_3") (pintype "passive"))
      (node (ref "U68") (pin "37") (pinfunction "PA14_37") (pintype "bidirectional"))
    )
    (net (code "39") (name "/SWDIO1") (class "Default")
      (node (ref "P1") (pin "2") (pinfunction "2_2") (pintype "passive"))
      (node (ref "U65") (pin "34") (pinfunction "PA13_34") (pintype "bidirectional"))
    )
    (net (code "40") (name "/SWDIO2") (class "Default")
      (node (ref "P2") (pin "2") (pinfunction "2_2") (pintype "passive"))
      (node (ref "U66") (pin "34") (pinfunction "PA13_34") (pintype "bidirectional"))
    )
    (net (code "41") (name "/SWDIO3") (class "Default")
      (node (ref "P3") (pin "2") (pinfunction "2_2") (pintype "passive"))
      (node (ref "U67") (pin "34") (pinfunction "PA13_34") (pintype "bidirectional"))
    )
    (net (code "42") (name "/SWDIO4") (class "Default")
      (node (ref "P4") (pin "2") (pinfunction "2_2") (pintype "passive"))
      (node (ref "U68") (pin "34") (pinfunction "PA13_34") (pintype "bidirectional"))
    )
    (net (code "43") (name "/USB_DM") (class "Default")
      (node (ref "J1") (pin "A7") (pinfunction "Dn1_A7") (pintype "bidirectional"))
      (node (ref "J1") (pin "B7") (pinfunction "Dn2_B7") (pintype "bidirectional"))
      (node (ref "U65") (pin "32") (pinfunction "PA11_32") (pintype "bidirectional"))
    )
    (net (code "44") (name "/USB_DP") (class "Default")
      (node (ref "J1") (pin "A6") (pinfunction "Dp1_A6") (pintype "bidirectional"))
      (node (ref "J1") (pin "B6") (pinfunction "Dp2_B6") (pintype "bidirectional"))
      (node (ref "U65") (pin "33") (pinfunction "PA12_33") (pintype "bidirectional"))
    )
    (net (code "45") (name "GND") (class "Default")
      (node (ref "C1") (pin "1") (pinfunction "1_1") (pintype "passive"))
      (node (ref "C10") (pin "1") (pinfunction "1_1") (pintype "passive"))
      (node (ref "C11") (pin "1") (pinfunction "1_1") (pintype "passive"))
      (node (ref "C12") (pin "1") (pinfunction "1_1") (pintype "passive"))
      (node (ref "C13") (pin "1") (pinfunction "1_1") (pintype "passive"))
      (node (ref "C14") (pin "1") (pinfunction "1_1") (pintype "passive"))
      (node (ref "C15") (pin "1") (pinfunction "1_1") (pintype "passive"))
      (node (ref "C16") (pin "1") (pinfunction "1_1") (pintype "passive"))
      (node (ref "C17") (pin "1") (pinfunction "1_1") (pintype "passive"))
      (node (ref "C18") (pin "1") (pinfunction "1_1") (pintype "passive"))
      (node (ref "C19") (pin "1") (pinfunction "1_1") (pintype "passive"))
      (node (ref "C2") (pin "1") (pinfunction "1_1") (pintype "passive"))
      (node (ref "C20") (pin "1") (pinfunction "1_1") (pintype "passive"))
      (node (ref "C3") (pin "1") (pinfunction "1_1") (pintype "passive"))
      (node (ref "C4") (pin "1") (pinfunction "1_1") (pintype "passive"))
      (node (ref "C5") (pin "1") (pinfunction "1_1") (pintype "passive"))
      (node (ref "C6") (pin "1") (pinfunction "1_1") (pintype "passive"))
      (node (ref "C7") (pin "1") (pinfunction "1_1") (pintype "passive"))
      (node (ref "C8") (pin "1") (pinfunction "1_1") (pintype "passive"))
      (node (ref "C9") (pin "1") (pinfunction "1_1") (pintype "passive"))
      (node (ref "J1") (pin "1") (pinfunction "MNT_1_1") (pintype "passive"))
      (node (ref "J1") (pin "2") (pinfunction "MNT_2_2") (pintype "passive"))
      (node (ref "J1") (pin "3") (pinfunction "MNT_3_3") (pintype "passive"))
      (node (ref "J1") (pin "4") (pinfunction "MNT_4_4") (pintype "passive"))
      (node (ref "J1") (pin "A1-B12") (pinfunction "GND_A1-B12") (pintype "power_in"))
      (node (ref "J1") (pin "B1-A12") (pinfunction "GND_B1-A12") (pintype "power_in"))
      (node (ref "P1") (pin "4") (pinfunction "4_4") (pintype "passive"))
      (node (ref "P2") (pin "4") (pinfunction "4_4") (pintype "passive"))
      (node (ref "P3") (pin "4") (pinfunction "4_4") (pintype "passive"))
      (node (ref "P4") (pin "4") (pinfunction "4_4") (pintype "passive"))
      (node (ref "R33") (pin "1") (pinfunction "1_1") (pintype "passive"))
      (node (ref "R34") (pin "1") (pinfunction "1_1") (pintype "passive"))
      (node (ref "R36") (pin "2") (pinfunction "2_2") (pintype "passive"))
      (node (ref "R37") (pin "2") (pinfunction "2_2") (pintype "passive"))
      (node (ref "R38") (pin "2") (pinfunction "2_2") (pintype "passive"))
      (node (ref "R39") (pin "2") (pinfunction "2_2") (pintype "passive"))
      (node (ref "R40") (pin "2") (pinfunction "2_2") (pintype "passive"))
      (node (ref "U1") (pin "A1") (pinfunction "VSA_A1") (pintype "power_in"))
      (node (ref "U10") (pin "A1") (pinfunction "VSA_A1") (pintype "power_in"))
      (node (ref "U11") (pin "A1") (pinfunction "VSA_A1") (pintype "power_in"))
      (node (ref "U12") (pin "A1") (pinfunction "VSA_A1") (pintype "power_in"))
      (node (ref "U13") (pin "A1") (pinfunction "VSA_A1") (pintype "power_in"))
      (node (ref "U14") (pin "A1") (pinfunction "VSA_A1") (pintype "power_in"))
      (node (ref "U15") (pin "A1") (pinfunction "VSA_A1") (pintype "power_in"))
      (node (ref "U16") (pin "A1") (pinfunction "VSA_A1") (pintype "power_in"))
      (node (ref "U17") (pin "A1") (pinfunction "VSA_A1") (pintype "power_in"))
      (node (ref "U18") (pin "A1") (pinfunction "VSA_A1") (pintype "power_in"))
      (node (ref "U19") (pin "A1") (pinfunction "VSA_A1") (pintype "power_in"))
      (node (ref "U2") (pin "A1") (pinfunction "VSA_A1") (pintype "power_in"))
      (node (ref "U20") (pin "A1") (pinfunction "VSA_A1") (pintype "power_in"))
      (node (ref "U21") (pin "A1") (pinfunction "VSA_A1") (pintype "power_in"))
      (node (ref "U22") (pin "A1") (pinfunction "VSA_A1") (pintype "power_in"))
      (node (ref "U23") (pin "A1") (pinfunction "VSA_A1") (pintype "power_in"))
      (node (ref "U24") (pin "A1") (pinfunction "VSA_A1") (pintype "power_in"))
      (node (ref "U25") (pin "A1") (pinfunction "VSA_A1") (pintype "power_in"))
      (node (ref "U26") (pin "A1") (pinfunction "VSA_A1") (pintype "power_in"))
      (node (ref "U27") (pin "A1") (pinfunction "VSA_A1") (pintype "power_in"))
      (node (ref "U28") (pin "A1") (pinfunction "VSA_A1") (pintype "power_in"))
      (node (ref "U29") (pin "A1") (pinfunction "VSA_A1") (pintype "power_in"))
      (node (ref "U3") (pin "A1") (pinfunction "VSA_A1") (pintype "power_in"))
      (node (ref "U30") (pin "A1") (pinfunction "VSA_A1") (pintype "power_in"))
      (node (ref "U31") (pin "A1") (pinfunction "VSA_A1") (pintype "power_in"))
      (node (ref "U32") (pin "A1") (pinfunction "VSA_A1") (pintype "power_in"))
      (node (ref "U33") (pin "A1") (pinfunction "VSA_A1") (pintype "power_in"))
      (node (ref "U34") (pin "A1") (pinfunction "VSA_A1") (pintype "power_in"))
      (node (ref "U35") (pin "A1") (pinfunction "VSA_A1") (pintype "power_in"))
      (node (ref "U36") (pin "A1") (pinfunction "VSA_A1") (pintype "power_in"))
      (node (ref "U37") (pin "A1") (pinfunction "VSA_A1") (pintype "power_in"))
      (node (ref "U38") (pin "A1") (pinfunction "VSA_A1") (pintype "power_in"))
      (node (ref "U39") (pin "A1") (pinfunction "VSA_A1") (pintype "power_in"))
      (node (ref "U4") (pin "A1") (pinfunction "VSA_A1") (pintype "power_in"))
      (node (ref "U40") (pin "A1") (pinfunction "VSA_A1") (pintype "power_in"))
      (node (ref "U41") (pin "A1") (pinfunction "VSA_A1") (pintype "power_in"))
      (node (ref "U42") (pin "A1") (pinfunction "VSA_A1") (pintype "power_in"))
      (node (ref "U43") (pin "A1") (pinfunction "VSA_A1") (pintype "power_in"))
      (node (ref "U44") (pin "A1") (pinfunction "VSA_A1") (pintype "power_in"))
      (node (ref "U45") (pin "A1") (pinfunction "VSA_A1") (pintype "power_in"))
      (node (ref "U46") (pin "A1") (pinfunction "VSA_A1") (pintype "power_in"))
      (node (ref "U47") (pin "A1") (pinfunction "VSA_A1") (pintype "power_in"))
      (node (ref "U48") (pin "A1") (pinfunction "VSA_A1") (pintype "power_in"))
      (node (ref "U49") (pin "A1") (pinfunction "VSA_A1") (pintype "power_in"))
      (node (ref "U5") (pin "A1") (pinfunction "VSA_A1") (pintype "power_in"))
      (node (ref "U50") (pin "A1") (pinfunction "VSA_A1") (pintype "power_in"))
      (node (ref "U51") (pin "A1") (pinfunction "VSA_A1") (pintype "power_in"))
      (node (ref "U52") (pin "A1") (pinfunction "VSA_A1") (pintype "power_in"))
      (node (ref "U53") (pin "A1") (pinfunction "VSA_A1") (pintype "power_in"))
      (node (ref "U54") (pin "A1") (pinfunction "VSA_A1") (pintype "power_in"))
      (node (ref "U55") (pin "A1") (pinfunction "VSA_A1") (pintype "power_in"))
      (node (ref "U56") (pin "A1") (pinfunction "VSA_A1") (pintype "power_in"))
      (node (ref "U57") (pin "A1") (pinfunction "VSA_A1") (pintype "power_in"))
      (node (ref "U58") (pin "A1") (pinfunction "VSA_A1") (pintype "power_in"))
      (node (ref "U59") (pin "A1") (pinfunction "VSA_A1") (pintype "power_in"))
      (node (ref "U6") (pin "A1") (pinfunction "VSA_A1") (pintype "power_in"))
      (node (ref "U60") (pin "A1") (pinfunction "VSA_A1") (pintype "power_in"))
      (node (ref "U61") (pin "A1") (pinfunction "VSA_A1") (pintype "power_in"))
      (node (ref "U62") (pin "A1") (pinfunction "VSA_A1") (pintype "power_in"))
      (node (ref "U63") (pin "A1") (pinfunction "VSA_A1") (pintype "power_in"))
      (node (ref "U64") (pin "A1") (pinfunction "VSA_A1") (pintype "power_in"))
      (node (ref "U65") (pin "23") (pinfunction "VSS_23") (pintype "power_in"))
      (node (ref "U65") (pin "35") (pinfunction "VSS_35") (pintype "power_in"))
      (node (ref "U65") (pin "47") (pinfunction "VSS_47") (pintype "power_in"))
      (node (ref "U65") (pin "49") (pinfunction "EPAD_49") (pintype "passive"))
      (node (ref "U65") (pin "8") (pinfunction "VSSA/VREF-_8") (pintype "power_in"))
      (node (ref "U66") (pin "23") (pinfunction "VSS_23") (pintype "power_in"))
      (node (ref "U66") (pin "35") (pinfunction "VSS_35") (pintype "power_in"))
      (node (ref "U66") (pin "47") (pinfunction "VSS_47") (pintype "power_in"))
      (node (ref "U66") (pin "49") (pinfunction "EPAD_49") (pintype "passive"))
      (node (ref "U66") (pin "8") (pinfunction "VSSA/VREF-_8") (pintype "power_in"))
      (node (ref "U67") (pin "23") (pinfunction "VSS_23") (pintype "power_in"))
      (node (ref "U67") (pin "35") (pinfunction "VSS_35") (pintype "power_in"))
      (node (ref "U67") (pin "47") (pinfunction "VSS_47") (pintype "power_in"))
      (node (ref "U67") (pin "49") (pinfunction "EPAD_49") (pintype "passive"))
      (node (ref "U67") (pin "8") (pinfunction "VSSA/VREF-_8") (pintype "power_in"))
      (node (ref "U68") (pin "23") (pinfunction "VSS_23") (pintype "power_in"))
      (node (ref "U68") (pin "35") (pinfunction "VSS_35") (pintype "power_in"))
      (node (ref "U68") (pin "47") (pinfunction "VSS_47") (pintype "power_in"))
      (node (ref "U68") (pin "49") (pinfunction "EPAD_49") (pintype "passive"))
      (node (ref "U68") (pin "8") (pinfunction "VSSA/VREF-_8") (pintype "power_in"))
      (node (ref "U69") (pin "1") (pinfunction "GND_1") (pintype "passive"))
      (node (ref "U7") (pin "A1") (pinfunction "VSA_A1") (pintype "power_in"))
      (node (ref "U70") (pin "2") (pinfunction "GND_2") (pintype "power_in"))
      (node (ref "U8") (pin "A1") (pinfunction "VSA_A1") (pintype "power_in"))
      (node (ref "U9") (pin "A1") (pinfunction "VSA_A1") (pintype "power_in"))
    )
    (net (code "46") (name "Net-(J1-CC1)") (class "Default")
      (node (ref "J1") (pin "A5") (pinfunction "CC1_A5") (pintype "bidirectional"))
      (node (ref "R33") (pin "2") (pinfunction "2_2") (pintype "passive"))
    )
    (net (code "47") (name "Net-(J1-CC2)") (class "Default")
      (node (ref "J1") (pin "B5") (pinfunction "CC2_B5") (pintype "bidirectional"))
      (node (ref "R34") (pin "2") (pinfunction "2_2") (pintype "passive"))
    )
    (net (code "48") (name "Net-(U65A-PH3-BOOT0)") (class "Default")
      (node (ref "R37") (pin "1") (pinfunction "1_1") (pintype "passive"))
      (node (ref "U65") (pin "44") (pinfunction "PH3-BOOT0_44") (pintype "bidirectional"))
    )
    (net (code "49") (name "Net-(U66A-PH3-BOOT0)") (class "Default")
      (node (ref "R38") (pin "1") (pinfunction "1_1") (pintype "passive"))
      (node (ref "U66") (pin "44") (pinfunction "PH3-BOOT0_44") (pintype "bidirectional"))
    )
    (net (code "50") (name "Net-(U67A-PH3-BOOT0)") (class "Default")
      (node (ref "R39") (pin "1") (pinfunction "1_1") (pintype "passive"))
      (node (ref "U67") (pin "44") (pinfunction "PH3-BOOT0_44") (pintype "bidirectional"))
    )
    (net (code "51") (name "Net-(U68A-PH3-BOOT0)") (class "Default")
      (node (ref "R40") (pin "1") (pinfunction "1_1") (pintype "passive"))
      (node (ref "U68") (pin "44") (pinfunction "PH3-BOOT0_44") (pintype "bidirectional"))
    )
    (net (code "52") (name "Net-(U69-FB)") (class "Default")
      (node (ref "R35") (pin "2") (pinfunction "2_2") (pintype "passive"))
      (node (ref "R36") (pin "1") (pinfunction "1_1") (pintype "passive"))
      (node (ref "U69") (pin "5") (pinfunction "FB_5") (pintype "input"))
    )
    (net (code "53") (name "Net-(U69-SW)") (class "Default")
      (node (ref "L1") (pin "1") (pinfunction "1_1") (pintype "passive"))
      (node (ref "U69") (pin "2") (pinfunction "SW_2") (pintype "output"))
    )
    (net (code "54") (name "VCC1V8") (class "Default")
      (node (ref "C10") (pin "2") (pinfunction "2_2") (pintype "passive"))
      (node (ref "C11") (pin "2") (pinfunction "2_2") (pintype "passive"))
      (node (ref "C12") (pin "2") (pinfunction "2_2") (pintype "passive"))
      (node (ref "C13") (pin "2") (pinfunction "2_2") (pintype "passive"))
      (node (ref "C14") (pin "2") (pinfunction "2_2") (pintype "passive"))
      (node (ref "C15") (pin "2") (pinfunction "2_2") (pintype "passive"))
      (node (ref "C16") (pin "2") (pinfunction "2_2") (pintype "passive"))
      (node (ref "C17") (pin "2") (pinfunction "2_2") (pintype "passive"))
      (node (ref "C18") (pin "2") (pinfunction "2_2") (pintype "passive"))
      (node (ref "C19") (pin "2") (pinfunction "2_2") (pintype "passive"))
      (node (ref "C2") (pin "2") (pinfunction "2_2") (pintype "passive"))
      (node (ref "C20") (pin "2") (pinfunction "2_2") (pintype "passive"))
      (node (ref "C5") (pin "2") (pinfunction "2_2") (pintype "passive"))
      (node (ref "C6") (pin "2") (pinfunction "2_2") (pintype "passive"))
      (node (ref "C7") (pin "2") (pinfunction "2_2") (pintype "passive"))
      (node (ref "C8") (pin "2") (pinfunction "2_2") (pintype "passive"))
      (node (ref "C9") (pin "2") (pinfunction "2_2") (pintype "passive"))
      (node (ref "L1") (pin "2") (pinfunction "2_2") (pintype "passive"))
      (node (ref "P1") (pin "1") (pinfunction "1_1") (pintype "passive"))
      (node (ref "P2") (pin "1") (pinfunction "1_1") (pintype "passive"))
      (node (ref "P3") (pin "1") (pinfunction "1_1") (pintype "passive"))
      (node (ref "P4") (pin "1") (pinfunction "1_1") (pintype "passive"))
      (node (ref "R1") (pin "2") (pinfunction "2_2") (pintype "passive"))
      (node (ref "R10") (pin "2") (pinfunction "2_2") (pintype "passive"))
      (node (ref "R11") (pin "2") (pinfunction "2_2") (pintype "passive"))
      (node (ref "R12") (pin "2") (pinfunction "2_2") (pintype "passive"))
      (node (ref "R13") (pin "2") (pinfunction "2_2") (pintype "passive"))
      (node (ref "R14") (pin "2") (pinfunction "2_2") (pintype "passive"))
      (node (ref "R15") (pin "2") (pinfunction "2_2") (pintype "passive"))
      (node (ref "R16") (pin "2") (pinfunction "2_2") (pintype "passive"))
      (node (ref "R17") (pin "2") (pinfunction "2_2") (pintype "passive"))
      (node (ref "R18") (pin "2") (pinfunction "2_2") (pintype "passive"))
      (node (ref "R19") (pin "2") (pinfunction "2_2") (pintype "passive"))
      (node (ref "R2") (pin "2") (pinfunction "2_2") (pintype "passive"))
      (node (ref "R20") (pin "2") (pinfunction "2_2") (pintype "passive"))
      (node (ref "R21") (pin "2") (pinfunction "2_2") (pintype "passive"))
      (node (ref "R22") (pin "2") (pinfunction "2_2") (pintype "passive"))
      (node (ref "R23") (pin "2") (pinfunction "2_2") (pintype "passive"))
      (node (ref "R24") (pin "2") (pinfunction "2_2") (pintype "passive"))
      (node (ref "R25") (pin "2") (pinfunction "2_2") (pintype "passive"))
      (node (ref "R26") (pin "2") (pinfunction "2_2") (pintype "passive"))
      (node (ref "R27") (pin "2") (pinfunction "2_2") (pintype "passive"))
      (node (ref "R28") (pin "2") (pinfunction "2_2") (pintype "passive"))
      (node (ref "R29") (pin "2") (pinfunction "2_2") (pintype "passive"))
      (node (ref "R3") (pin "2") (pinfunction "2_2") (pintype "passive"))
      (node (ref "R30") (pin "2") (pinfunction "2_2") (pintype "passive"))
      (node (ref "R31") (pin "2") (pinfunction "2_2") (pintype "passive"))
      (node (ref "R32") (pin "2") (pinfunction "2_2") (pintype "passive"))
      (node (ref "R35") (pin "1") (pinfunction "1_1") (pintype "passive"))
      (node (ref "R4") (pin "2") (pinfunction "2_2") (pintype "passive"))
      (node (ref "R5") (pin "2") (pinfunction "2_2") (pintype "passive"))
      (node (ref "R6") (pin "2") (pinfunction "2_2") (pintype "passive"))
      (node (ref "R7") (pin "2") (pinfunction "2_2") (pintype "passive"))
      (node (ref "R8") (pin "2") (pinfunction "2_2") (pintype "passive"))
      (node (ref "R9") (pin "2") (pinfunction "2_2") (pintype "passive"))
      (node (ref "U1") (pin "B1") (pinfunction "VDD_B1") (pintype "power_in"))
      (node (ref "U10") (pin "B1") (pinfunction "VDD_B1") (pintype "power_in"))
      (node (ref "U11") (pin "B1") (pinfunction "VDD_B1") (pintype "power_in"))
      (node (ref "U12") (pin "B1") (pinfunction "VDD_B1") (pintype "power_in"))
      (node (ref "U13") (pin "B1") (pinfunction "VDD_B1") (pintype "power_in"))
      (node (ref "U14") (pin "B1") (pinfunction "VDD_B1") (pintype "power_in"))
      (node (ref "U15") (pin "B1") (pinfunction "VDD_B1") (pintype "power_in"))
      (node (ref "U16") (pin "B1") (pinfunction "VDD_B1") (pintype "power_in"))
      (node (ref "U17") (pin "B1") (pinfunction "VDD_B1") (pintype "power_in"))
      (node (ref "U18") (pin "B1") (pinfunction "VDD_B1") (pintype "power_in"))
      (node (ref "U19") (pin "B1") (pinfunction "VDD_B1") (pintype "power_in"))
      (node (ref "U2") (pin "B1") (pinfunction "VDD_B1") (pintype "power_in"))
      (node (ref "U20") (pin "B1") (pinfunction "VDD_B1") (pintype "power_in"))
      (node (ref "U21") (pin "B1") (pinfunction "VDD_B1") (pintype "power_in"))
      (node (ref "U22") (pin "B1") (pinfunction "VDD_B1") (pintype "power_in"))
      (node (ref "U23") (pin "B1") (pinfunction "VDD_B1") (pintype "power_in"))
      (node (ref "U24") (pin "B1") (pinfunction "VDD_B1") (pintype "power_in"))
      (node (ref "U25") (pin "B1") (pinfunction "VDD_B1") (pintype "power_in"))
      (node (ref "U26") (pin "B1") (pinfunction "VDD_B1") (pintype "power_in"))
      (node (ref "U27") (pin "B1") (pinfunction "VDD_B1") (pintype "power_in"))
      (node (ref "U28") (pin "B1") (pinfunction "VDD_B1") (pintype "power_in"))
      (node (ref "U29") (pin "B1") (pinfunction "VDD_B1") (pintype "power_in"))
      (node (ref "U3") (pin "B1") (pinfunction "VDD_B1") (pintype "power_in"))
      (node (ref "U30") (pin "B1") (pinfunction "VDD_B1") (pintype "power_in"))
      (node (ref "U31") (pin "B1") (pinfunction "VDD_B1") (pintype "power_in"))
      (node (ref "U32") (pin "B1") (pinfunction "VDD_B1") (pintype "power_in"))
      (node (ref "U33") (pin "B1") (pinfunction "VDD_B1") (pintype "power_in"))
      (node (ref "U34") (pin "B1") (pinfunction "VDD_B1") (pintype "power_in"))
      (node (ref "U35") (pin "B1") (pinfunction "VDD_B1") (pintype "power_in"))
      (node (ref "U36") (pin "B1") (pinfunction "VDD_B1") (pintype "power_in"))
      (node (ref "U37") (pin "B1") (pinfunction "VDD_B1") (pintype "power_in"))
      (node (ref "U38") (pin "B1") (pinfunction "VDD_B1") (pintype "power_in"))
      (node (ref "U39") (pin "B1") (pinfunction "VDD_B1") (pintype "power_in"))
      (node (ref "U4") (pin "B1") (pinfunction "VDD_B1") (pintype "power_in"))
      (node (ref "U40") (pin "B1") (pinfunction "VDD_B1") (pintype "power_in"))
      (node (ref "U41") (pin "B1") (pinfunction "VDD_B1") (pintype "power_in"))
      (node (ref "U42") (pin "B1") (pinfunction "VDD_B1") (pintype "power_in"))
      (node (ref "U43") (pin "B1") (pinfunction "VDD_B1") (pintype "power_in"))
      (node (ref "U44") (pin "B1") (pinfunction "VDD_B1") (pintype "power_in"))
      (node (ref "U45") (pin "B1") (pinfunction "VDD_B1") (pintype "power_in"))
      (node (ref "U46") (pin "B1") (pinfunction "VDD_B1") (pintype "power_in"))
      (node (ref "U47") (pin "B1") (pinfunction "VDD_B1") (pintype "power_in"))
      (node (ref "U48") (pin "B1") (pinfunction "VDD_B1") (pintype "power_in"))
      (node (ref "U49") (pin "B1") (pinfunction "VDD_B1") (pintype "power_in"))
      (node (ref "U5") (pin "B1") (pinfunction "VDD_B1") (pintype "power_in"))
      (node (ref "U50") (pin "B1") (pinfunction "VDD_B1") (pintype "power_in"))
      (node (ref "U51") (pin "B1") (pinfunction "VDD_B1") (pintype "power_in"))
      (node (ref "U52") (pin "B1") (pinfunction "VDD_B1") (pintype "power_in"))
      (node (ref "U53") (pin "B1") (pinfunction "VDD_B1") (pintype "power_in"))
      (node (ref "U54") (pin "B1") (pinfunction "VDD_B1") (pintype "power_in"))
      (node (ref "U55") (pin "B1") (pinfunction "VDD_B1") (pintype "power_in"))
      (node (ref "U56") (pin "B1") (pinfunction "VDD_B1") (pintype "power_in"))
      (node (ref "U57") (pin "B1") (pinfunction "VDD_B1") (pintype "power_in"))
      (node (ref "U58") (pin "B1") (pinfunction "VDD_B1") (pintype "power_in"))
      (node (ref "U59") (pin "B1") (pinfunction "VDD_B1") (pintype "power_in"))
      (node (ref "U6") (pin "B1") (pinfunction "VDD_B1") (pintype "power_in"))
      (node (ref "U60") (pin "B1") (pinfunction "VDD_B1") (pintype "power_in"))
      (node (ref "U61") (pin "B1") (pinfunction "VDD_B1") (pintype "power_in"))
      (node (ref "U62") (pin "B1") (pinfunction "VDD_B1") (pintype "power_in"))
      (node (ref "U63") (pin "B1") (pinfunction "VDD_B1") (pintype "power_in"))
      (node (ref "U64") (pin "B1") (pinfunction "VDD_B1") (pintype "power_in"))
      (node (ref "U65") (pin "1") (pinfunction "VBAT_1") (pintype "power_in"))
      (node (ref "U65") (pin "24") (pinfunction "VDD_24") (pintype "power_in"))
      (node (ref "U65") (pin "48") (pinfunction "VDD_48") (pintype "power_in"))
      (node (ref "U65") (pin "9") (pinfunction "VDDA/VREF+_9") (pintype "power_in"))
      (node (ref "U66") (pin "1") (pinfunction "VBAT_1") (pintype "power_in"))
      (node (ref "U66") (pin "24") (pinfunction "VDD_24") (pintype "power_in"))
      (node (ref "U66") (pin "48") (pinfunction "VDD_48") (pintype "power_in"))
      (node (ref "U66") (pin "9") (pinfunction "VDDA/VREF+_9") (pintype "power_in"))
      (node (ref "U67") (pin "1") (pinfunction "VBAT_1") (pintype "power_in"))
      (node (ref "U67") (pin "24") (pinfunction "VDD_24") (pintype "power_in"))
      (node (ref "U67") (pin "48") (pinfunction "VDD_48") (pintype "power_in"))
      (node (ref "U67") (pin "9") (pinfunction "VDDA/VREF+_9") (pintype "power_in"))
      (node (ref "U68") (pin "1") (pinfunction "VBAT_1") (pintype "power_in"))
      (node (ref "U68") (pin "24") (pinfunction "VDD_24") (pintype "power_in"))
      (node (ref "U68") (pin "48") (pinfunction "VDD_48") (pintype "power_in"))
      (node (ref "U68") (pin "9") (pinfunction "VDDA/VREF+_9") (pintype "power_in"))
      (node (ref "U7") (pin "B1") (pinfunction "VDD_B1") (pintype "power_in"))
      (node (ref "U8") (pin "B1") (pinfunction "VDD_B1") (pintype "power_in"))
      (node (ref "U9") (pin "B1") (pinfunction "VDD_B1") (pintype "power_in"))
    )
    (net (code "55") (name "VCC3V3") (class "Default")
      (node (ref "C4") (pin "2") (pinfunction "2_2") (pintype "passive"))
      (node (ref "U65") (pin "36") (pinfunction "VDDUSB_36") (pintype "power_in"))
      (node (ref "U70") (pin "5") (pinfunction "OUT_5") (pintype "power_in"))
    )
    (net (code "56") (name "unconnected-(J1-SBU1-PadA8)") (class "Default")
      (node (ref "J1") (pin "A8") (pinfunction "SBU1_A8") (pintype "bidirectional"))
    )
    (net (code "57") (name "unconnected-(J1-SBU2-PadB8)") (class "Default")
      (node (ref "J1") (pin "B8") (pinfunction "SBU2_B8") (pintype "bidirectional"))
    )
    (net (code "58") (name "unconnected-(U65A-PA0-Pad10)") (class "Default")
      (node (ref "U65") (pin "10") (pinfunction "PA0_10") (pintype "bidirectional"))
    )
    (net (code "59") (name "unconnected-(U65A-PA1-Pad11)") (class "Default")
      (node (ref "U65") (pin "11") (pinfunction "PA1_11") (pintype "bidirectional"))
    )
    (net (code "60") (name "unconnected-(U65A-PA2-Pad12)") (class "Default")
      (node (ref "U65") (pin "12") (pinfunction "PA2_12") (pintype "bidirectional"))
    )
    (net (code "61") (name "unconnected-(U65A-PA3-Pad13)") (class "Default")
      (node (ref "U65") (pin "13") (pinfunction "PA3_13") (pintype "bidirectional"))
    )
    (net (code "62") (name "unconnected-(U65A-PA4-Pad14)") (class "Default")
      (node (ref "U65") (pin "14") (pinfunction "PA4_14") (pintype "bidirectional"))
    )
    (net (code "63") (name "unconnected-(U65A-PA5-Pad15)") (class "Default")
      (node (ref "U65") (pin "15") (pinfunction "PA5_15") (pintype "bidirectional"))
    )
    (net (code "64") (name "unconnected-(U65A-PA6-Pad16)") (class "Default")
      (node (ref "U65") (pin "16") (pinfunction "PA6_16") (pintype "bidirectional"))
    )
    (net (code "65") (name "unconnected-(U65A-PA8-Pad29)") (class "Default")
      (node (ref "U65") (pin "29") (pinfunction "PA8_29") (pintype "bidirectional"))
    )
    (net (code "66") (name "unconnected-(U65A-PA15-Pad38)") (class "Default")
      (node (ref "U65") (pin "38") (pinfunction "PA15_38") (pintype "bidirectional"))
    )
    (net (code "67") (name "unconnected-(U65A-PB0-Pad18)") (class "Default")
      (node (ref "U65") (pin "18") (pinfunction "PB0_18") (pintype "bidirectional"))
    )
    (net (code "68") (name "unconnected-(U65A-PB1-Pad19)") (class "Default")
      (node (ref "U65") (pin "19") (pinfunction "PB1_19") (pintype "bidirectional"))
    )
    (net (code "69") (name "unconnected-(U65A-PB2-Pad20)") (class "Default")
      (node (ref "U65") (pin "20") (pinfunction "PB2_20") (pintype "bidirectional"))
    )
    (net (code "70") (name "unconnected-(U65A-PB3-Pad39)") (class "Default")
      (node (ref "U65") (pin "39") (pinfunction "PB3_39") (pintype "bidirectional"))
    )
    (net (code "71") (name "unconnected-(U65A-PB5-Pad41)") (class "Default")
      (node (ref "U65") (pin "41") (pinfunction "PB5_41") (pintype "bidirectional"))
    )
    (net (code "72") (name "unconnected-(U65A-PB8-Pad45)") (class "Default")
      (node (ref "U65") (pin "45") (pinfunction "PB8_45") (pintype "bidirectional"))
    )
    (net (code "73") (name "unconnected-(U65A-PB9-Pad46)") (class "Default")
      (node (ref "U65") (pin "46") (pinfunction "PB9_46") (pintype "bidirectional"))
    )
    (net (code "74") (name "unconnected-(U65A-PB12-Pad25)") (class "Default")
      (node (ref "U65") (pin "25") (pinfunction "PB12_25") (pintype "bidirectional"))
    )
    (net (code "75") (name "unconnected-(U65A-PB13-Pad26)") (class "Default")
      (node (ref "U65") (pin "26") (pinfunction "PB13_26") (pintype "bidirectional"))
    )
    (net (code "76") (name "unconnected-(U65A-PB14-Pad27)") (class "Default")
      (node (ref "U65") (pin "27") (pinfunction "PB14_27") (pintype "bidirectional"))
    )
    (net (code "77") (name "unconnected-(U65A-PB15-Pad28)") (class "Default")
      (node (ref "U65") (pin "28") (pinfunction "PB15_28") (pintype "bidirectional"))
    )
    (net (code "78") (name "unconnected-(U65A-PC13-Pad2)") (class "Default")
      (node (ref "U65") (pin "2") (pinfunction "PC13_2") (pintype "bidirectional"))
    )
    (net (code "79") (name "unconnected-(U65A-PC14-OSC32_IN-Pad3)") (class "Default")
      (node (ref "U65") (pin "3") (pinfunction "PC14-OSC32_IN_3") (pintype "bidirectional"))
    )
    (net (code "80") (name "unconnected-(U65A-PC15-OSC32_OUT-Pad4)") (class "Default")
      (node (ref "U65") (pin "4") (pinfunction "PC15-OSC32_OUT_4") (pintype "bidirectional"))
    )
    (net (code "81") (name "unconnected-(U65A-PH0-OSC_IN-Pad5)") (class "Default")
      (node (ref "U65") (pin "5") (pinfunction "PH0-OSC_IN_5") (pintype "bidirectional"))
    )
    (net (code "82") (name "unconnected-(U65A-PH1-OSC_OUT-Pad6)") (class "Default")
      (node (ref "U65") (pin "6") (pinfunction "PH1-OSC_OUT_6") (pintype "bidirectional"))
    )
    (net (code "83") (name "unconnected-(U66A-PA0-Pad10)") (class "Default")
      (node (ref "U66") (pin "10") (pinfunction "PA0_10") (pintype "bidirectional"))
    )
    (net (code "84") (name "unconnected-(U66A-PA1-Pad11)") (class "Default")
      (node (ref "U66") (pin "11") (pinfunction "PA1_11") (pintype "bidirectional"))
    )
    (net (code "85") (name "unconnected-(U66A-PA2-Pad12)") (class "Default")
      (node (ref "U66") (pin "12") (pinfunction "PA2_12") (pintype "bidirectional"))
    )
    (net (code "86") (name "unconnected-(U66A-PA3-Pad13)") (class "Default")
      (node (ref "U66") (pin "13") (pinfunction "PA3_13") (pintype "bidirectional"))
    )
    (net (code "87") (name "unconnected-(U66A-PA4-Pad14)") (class "Default")
      (node (ref "U66") (pin "14") (pinfunction "PA4_14") (pintype "bidirectional"))
    )
    (net (code "88") (name "unconnected-(U66A-PA5-Pad15)") (class "Default")
      (node (ref "U66") (pin "15") (pinfunction "PA5_15") (pintype "bidirectional"))
    )
    (net (code "89") (name "unconnected-(U66A-PA6-Pad16)") (class "Default")
      (node (ref "U66") (pin "16") (pinfunction "PA6_16") (pintype "bidirectional"))
    )
    (net (code "90") (name "unconnected-(U66A-PA8-Pad29)") (class "Default")
      (node (ref "U66") (pin "29") (pinfunction "PA8_29") (pintype "bidirectional"))
    )
    (net (code "91") (name "unconnected-(U66A-PA11-Pad32)") (class "Default")
      (node (ref "U66") (pin "32") (pinfunction "PA11_32") (pintype "bidirectional"))
    )
    (net (code "92") (name "unconnected-(U66A-PA12-Pad33)") (class "Default")
      (node (ref "U66") (pin "33") (pinfunction "PA12_33") (pintype "bidirectional"))
    )
    (net (code "93") (name "unconnected-(U66A-PA15-Pad38)") (class "Default")
      (node (ref "U66") (pin "38") (pinfunction "PA15_38") (pintype "bidirectional"))
    )
    (net (code "94") (name "unconnected-(U66A-PB0-Pad18)") (class "Default")
      (node (ref "U66") (pin "18") (pinfunction "PB0_18") (pintype "bidirectional"))
    )
    (net (code "95") (name "unconnected-(U66A-PB1-Pad19)") (class "Default")
      (node (ref "U66") (pin "19") (pinfunction "PB1_19") (pintype "bidirectional"))
    )
    (net (code "96") (name "unconnected-(U66A-PB2-Pad20)") (class "Default")
      (node (ref "U66") (pin "20") (pinfunction "PB2_20") (pintype "bidirectional"))
    )
    (net (code "97") (name "unconnected-(U66A-PB3-Pad39)") (class "Default")
      (node (ref "U66") (pin "39") (pinfunction "PB3_39") (pintype "bidirectional"))
    )
    (net (code "98") (name "unconnected-(U66A-PB5-Pad41)") (class "Default")
      (node (ref "U66") (pin "41") (pinfunction "PB5_41") (pintype "bidirectional"))
    )
    (net (code "99") (name "unconnected-(U66A-PB8-Pad45)") (class "Default")
      (node (ref "U66") (pin "45") (pinfunction "PB8_45") (pintype "bidirectional"))
    )
    (net (code "100") (name "unconnected-(U66A-PB9-Pad46)") (class "Default")
      (node (ref "U66") (pin "46") (pinfunction "PB9_46") (pintype "bidirectional"))
    )
    (net (code "101") (name "unconnected-(U66A-PB12-Pad25)") (class "Default")
      (node (ref "U66") (pin "25") (pinfunction "PB12_25") (pintype "bidirectional"))
    )
    (net (code "102") (name "unconnected-(U66A-PB13-Pad26)") (class "Default")
      (node (ref "U66") (pin "26") (pinfunction "PB13_26") (pintype "bidirectional"))
    )
    (net (code "103") (name "unconnected-(U66A-PB14-Pad27)") (class "Default")
      (node (ref "U66") (pin "27") (pinfunction "PB14_27") (pintype "bidirectional"))
    )
    (net (code "104") (name "unconnected-(U66A-PB15-Pad28)") (class "Default")
      (node (ref "U66") (pin "28") (pinfunction "PB15_28") (pintype "bidirectional"))
    )
    (net (code "105") (name "unconnected-(U66A-PC13-Pad2)") (class "Default")
      (node (ref "U66") (pin "2") (pinfunction "PC13_2") (pintype "bidirectional"))
    )
    (net (code "106") (name "unconnected-(U66A-PC14-OSC32_IN-Pad3)") (class "Default")
      (node (ref "U66") (pin "3") (pinfunction "PC14-OSC32_IN_3") (pintype "bidirectional"))
    )
    (net (code "107") (name "unconnected-(U66A-PC15-OSC32_OUT-Pad4)") (class "Default")
      (node (ref "U66") (pin "4") (pinfunction "PC15-OSC32_OUT_4") (pintype "bidirectional"))
    )
    (net (code "108") (name "unconnected-(U66A-PH0-OSC_IN-Pad5)") (class "Default")
      (node (ref "U66") (pin "5") (pinfunction "PH0-OSC_IN_5") (pintype "bidirectional"))
    )
    (net (code "109") (name "unconnected-(U66A-PH1-OSC_OUT-Pad6)") (class "Default")
      (node (ref "U66") (pin "6") (pinfunction "PH1-OSC_OUT_6") (pintype "bidirectional"))
    )
    (net (code "110") (name "unconnected-(U66B-VDDUSB-Pad36)") (class "Default")
      (node (ref "U66") (pin "36") (pinfunction "VDDUSB_36") (pintype "power_in"))
    )
    (net (code "111") (name "unconnected-(U67A-PA0-Pad10)") (class "Default")
      (node (ref "U67") (pin "10") (pinfunction "PA0_10") (pintype "bidirectional"))
    )
    (net (code "112") (name "unconnected-(U67A-PA1-Pad11)") (class "Default")
      (node (ref "U67") (pin "11") (pinfunction "PA1_11") (pintype "bidirectional"))
    )
    (net (code "113") (name "unconnected-(U67A-PA2-Pad12)") (class "Default")
      (node (ref "U67") (pin "12") (pinfunction "PA2_12") (pintype "bidirectional"))
    )
    (net (code "114") (name "unconnected-(U67A-PA3-Pad13)") (class "Default")
      (node (ref "U67") (pin "13") (pinfunction "PA3_13") (pintype "bidirectional"))
    )
    (net (code "115") (name "unconnected-(U67A-PA4-Pad14)") (class "Default")
      (node (ref "U67") (pin "14") (pinfunction "PA4_14") (pintype "bidirectional"))
    )
    (net (code "116") (name "unconnected-(U67A-PA5-Pad15)") (class "Default")
      (node (ref "U67") (pin "15") (pinfunction "PA5_15") (pintype "bidirectional"))
    )
    (net (code "117") (name "unconnected-(U67A-PA6-Pad16)") (class "Default")
      (node (ref "U67") (pin "16") (pinfunction "PA6_16") (pintype "bidirectional"))
    )
    (net (code "118") (name "unconnected-(U67A-PA8-Pad29)") (class "Default")
      (node (ref "U67") (pin "29") (pinfunction "PA8_29") (pintype "bidirectional"))
    )
    (net (code "119") (name "unconnected-(U67A-PA11-Pad32)") (class "Default")
      (node (ref "U67") (pin "32") (pinfunction "PA11_32") (pintype "bidirectional"))
    )
    (net (code "120") (name "unconnected-(U67A-PA12-Pad33)") (class "Default")
      (node (ref "U67") (pin "33") (pinfunction "PA12_33") (pintype "bidirectional"))
    )
    (net (code "121") (name "unconnected-(U67A-PA15-Pad38)") (class "Default")
      (node (ref "U67") (pin "38") (pinfunction "PA15_38") (pintype "bidirectional"))
    )
    (net (code "122") (name "unconnected-(U67A-PB0-Pad18)") (class "Default")
      (node (ref "U67") (pin "18") (pinfunction "PB0_18") (pintype "bidirectional"))
    )
    (net (code "123") (name "unconnected-(U67A-PB1-Pad19)") (class "Default")
      (node (ref "U67") (pin "19") (pinfunction "PB1_19") (pintype "bidirectional"))
    )
    (net (code "124") (name "unconnected-(U67A-PB2-Pad20)") (class "Default")
      (node (ref "U67") (pin "20") (pinfunction "PB2_20") (pintype "bidirectional"))
    )
    (net (code "125") (name "unconnected-(U67A-PB3-Pad39)") (class "Default")
      (node (ref "U67") (pin "39") (pinfunction "PB3_39") (pintype "bidirectional"))
    )
    (net (code "126") (name "unconnected-(U67A-PB5-Pad41)") (class "Default")
      (node (ref "U67") (pin "41") (pinfunction "PB5_41") (pintype "bidirectional"))
    )
    (net (code "127") (name "unconnected-(U67A-PB8-Pad45)") (class "Default")
      (node (ref "U67") (pin "45") (pinfunction "PB8_45") (pintype "bidirectional"))
    )
    (net (code "128") (name "unconnected-(U67A-PB9-Pad46)") (class "Default")
      (node (ref "U67") (pin "46") (pinfunction "PB9_46") (pintype "bidirectional"))
    )
    (net (code "129") (name "unconnected-(U67A-PB12-Pad25)") (class "Default")
      (node (ref "U67") (pin "25") (pinfunction "PB12_25") (pintype "bidirectional"))
    )
    (net (code "130") (name "unconnected-(U67A-PB13-Pad26)") (class "Default")
      (node (ref "U67") (pin "26") (pinfunction "PB13_26") (pintype "bidirectional"))
    )
    (net (code "131") (name "unconnected-(U67A-PB14-Pad27)") (class "Default")
      (node (ref "U67") (pin "27") (pinfunction "PB14_27") (pintype "bidirectional"))
    )
    (net (code "132") (name "unconnected-(U67A-PB15-Pad28)") (class "Default")
      (node (ref "U67") (pin "28") (pinfunction "PB15_28") (pintype "bidirectional"))
    )
    (net (code "133") (name "unconnected-(U67A-PC13-Pad2)") (class "Default")
      (node (ref "U67") (pin "2") (pinfunction "PC13_2") (pintype "bidirectional"))
    )
    (net (code "134") (name "unconnected-(U67A-PC14-OSC32_IN-Pad3)") (class "Default")
      (node (ref "U67") (pin "3") (pinfunction "PC14-OSC32_IN_3") (pintype "bidirectional"))
    )
    (net (code "135") (name "unconnected-(U67A-PC15-OSC32_OUT-Pad4)") (class "Default")
      (node (ref "U67") (pin "4") (pinfunction "PC15-OSC32_OUT_4") (pintype "bidirectional"))
    )
    (net (code "136") (name "unconnected-(U67A-PH0-OSC_IN-Pad5)") (class "Default")
      (node (ref "U67") (pin "5") (pinfunction "PH0-OSC_IN_5") (pintype "bidirectional"))
    )
    (net (code "137") (name "unconnected-(U67A-PH1-OSC_OUT-Pad6)") (class "Default")
      (node (ref "U67") (pin "6") (pinfunction "PH1-OSC_OUT_6") (pintype "bidirectional"))
    )
    (net (code "138") (name "unconnected-(U67B-VDDUSB-Pad36)") (class "Default")
      (node (ref "U67") (pin "36") (pinfunction "VDDUSB_36") (pintype "power_in"))
    )
    (net (code "139") (name "unconnected-(U68A-PA0-Pad10)") (class "Default")
      (node (ref "U68") (pin "10") (pinfunction "PA0_10") (pintype "bidirectional"))
    )
    (net (code "140") (name "unconnected-(U68A-PA1-Pad11)") (class "Default")
      (node (ref "U68") (pin "11") (pinfunction "PA1_11") (pintype "bidirectional"))
    )
    (net (code "141") (name "unconnected-(U68A-PA2-Pad12)") (class "Default")
      (node (ref "U68") (pin "12") (pinfunction "PA2_12") (pintype "bidirectional"))
    )
    (net (code "142") (name "unconnected-(U68A-PA3-Pad13)") (class "Default")
      (node (ref "U68") (pin "13") (pinfunction "PA3_13") (pintype "bidirectional"))
    )
    (net (code "143") (name "unconnected-(U68A-PA4-Pad14)") (class "Default")
      (node (ref "U68") (pin "14") (pinfunction "PA4_14") (pintype "bidirectional"))
    )
    (net (code "144") (name "unconnected-(U68A-PA5-Pad15)") (class "Default")
      (node (ref "U68") (pin "15") (pinfunction "PA5_15") (pintype "bidirectional"))
    )
    (net (code "145") (name "unconnected-(U68A-PA6-Pad16)") (class "Default")
      (node (ref "U68") (pin "16") (pinfunction "PA6_16") (pintype "bidirectional"))
    )
    (net (code "146") (name "unconnected-(U68A-PA8-Pad29)") (class "Default")
      (node (ref "U68") (pin "29") (pinfunction "PA8_29") (pintype "bidirectional"))
    )
    (net (code "147") (name "unconnected-(U68A-PA11-Pad32)") (class "Default")
      (node (ref "U68") (pin "32") (pinfunction "PA11_32") (pintype "bidirectional"))
    )
    (net (code "148") (name "unconnected-(U68A-PA12-Pad33)") (class "Default")
      (node (ref "U68") (pin "33") (pinfunction "PA12_33") (pintype "bidirectional"))
    )
    (net (code "149") (name "unconnected-(U68A-PA15-Pad38)") (class "Default")
      (node (ref "U68") (pin "38") (pinfunction "PA15_38") (pintype "bidirectional"))
    )
    (net (code "150") (name "unconnected-(U68A-PB0-Pad18)") (class "Default")
      (node (ref "U68") (pin "18") (pinfunction "PB0_18") (pintype "bidirectional"))
    )
    (net (code "151") (name "unconnected-(U68A-PB1-Pad19)") (class "Default")
      (node (ref "U68") (pin "19") (pinfunction "PB1_19") (pintype "bidirectional"))
    )
    (net (code "152") (name "unconnected-(U68A-PB2-Pad20)") (class "Default")
      (node (ref "U68") (pin "20") (pinfunction "PB2_20") (pintype "bidirectional"))
    )
    (net (code "153") (name "unconnected-(U68A-PB3-Pad39)") (class "Default")
      (node (ref "U68") (pin "39") (pinfunction "PB3_39") (pintype "bidirectional"))
    )
    (net (code "154") (name "unconnected-(U68A-PB5-Pad41)") (class "Default")
      (node (ref "U68") (pin "41") (pinfunction "PB5_41") (pintype "bidirectional"))
    )
    (net (code "155") (name "unconnected-(U68A-PB8-Pad45)") (class "Default")
      (node (ref "U68") (pin "45") (pinfunction "PB8_45") (pintype "bidirectional"))
    )
    (net (code "156") (name "unconnected-(U68A-PB9-Pad46)") (class "Default")
      (node (ref "U68") (pin "46") (pinfunction "PB9_46") (pintype "bidirectional"))
    )
    (net (code "157") (name "unconnected-(U68A-PB12-Pad25)") (class "Default")
      (node (ref "U68") (pin "25") (pinfunction "PB12_25") (pintype "bidirectional"))
    )
    (net (code "158") (name "unconnected-(U68A-PB13-Pad26)") (class "Default")
      (node (ref "U68") (pin "26") (pinfunction "PB13_26") (pintype "bidirectional"))
    )
    (net (code "159") (name "unconnected-(U68A-PB14-Pad27)") (class "Default")
      (node (ref "U68") (pin "27") (pinfunction "PB14_27") (pintype "bidirectional"))
    )
    (net (code "160") (name "unconnected-(U68A-PB15-Pad28)") (class "Default")
      (node (ref "U68") (pin "28") (pinfunction "PB15_28") (pintype "bidirectional"))
    )
    (net (code "161") (name "unconnected-(U68A-PC13-Pad2)") (class "Default")
      (node (ref "U68") (pin "2") (pinfunction "PC13_2") (pintype "bidirectional"))
    )
    (net (code "162") (name "unconnected-(U68A-PC14-OSC32_IN-Pad3)") (class "Default")
      (node (ref "U68") (pin "3") (pinfunction "PC14-OSC32_IN_3") (pintype "bidirectional"))
    )
    (net (code "163") (name "unconnected-(U68A-PC15-OSC32_OUT-Pad4)") (class "Default")
      (node (ref "U68") (pin "4") (pinfunction "PC15-OSC32_OUT_4") (pintype "bidirectional"))
    )
    (net (code "164") (name "unconnected-(U68A-PH0-OSC_IN-Pad5)") (class "Default")
      (node (ref "U68") (pin "5") (pinfunction "PH0-OSC_IN_5") (pintype "bidirectional"))
    )
    (net (code "165") (name "unconnected-(U68A-PH1-OSC_OUT-Pad6)") (class "Default")
      (node (ref "U68") (pin "6") (pinfunction "PH1-OSC_OUT_6") (pintype "bidirectional"))
    )
    (net (code "166") (name "unconnected-(U68B-VDDUSB-Pad36)") (class "Default")
      (node (ref "U68") (pin "36") (pinfunction "VDDUSB_36") (pintype "power_in"))
    )
    (net (code "167") (name "unconnected-(U69-PG-Pad6)") (class "Default")
      (node (ref "U69") (pin "6") (pinfunction "PG_6") (pintype "output"))
    )
    (net (code "168") (name "unconnected-(U70-NC-Pad4)") (class "Default")
      (node (ref "U70") (pin "4") (pinfunction "NC_4") (pintype "passive"))
    )
  )
)
